# demo_dermis_main_testboard_dig.net
KiCad netlist of a schematic drawn in Altium Designer
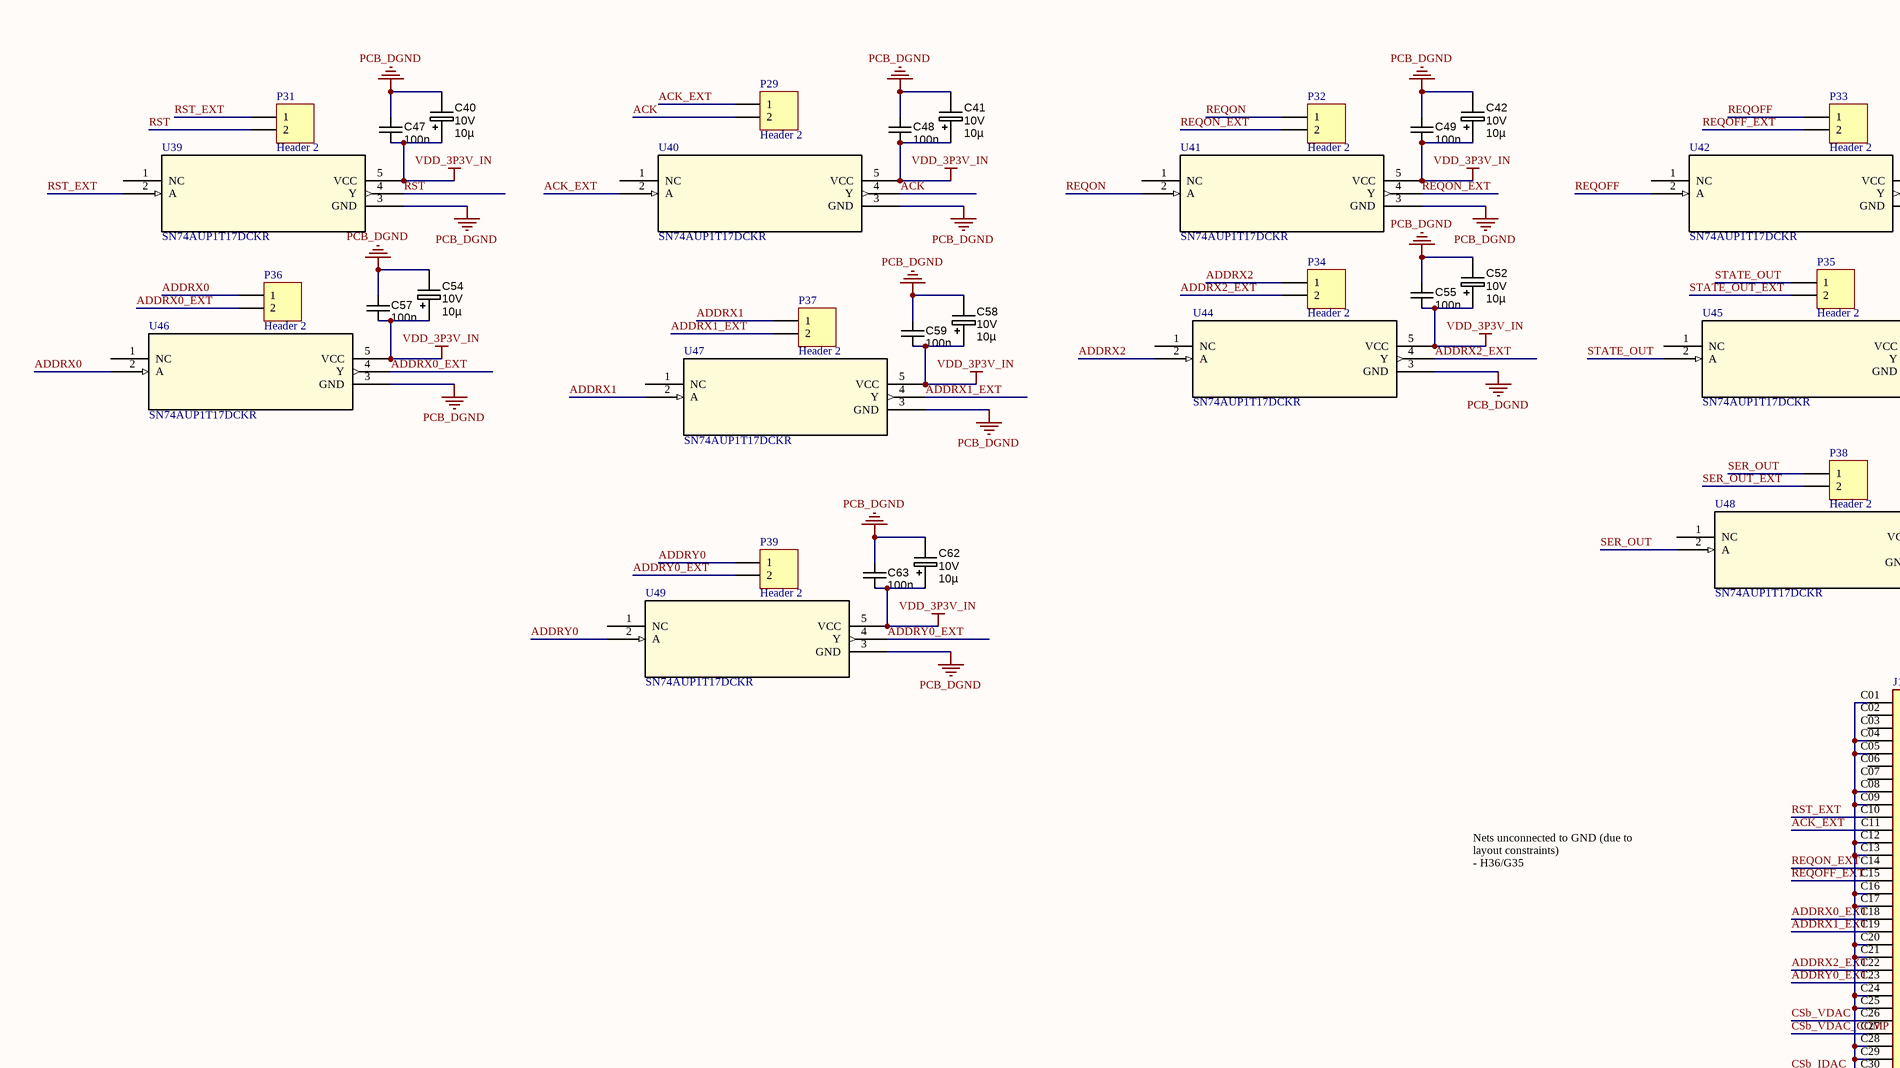
[diagram p0: demo_dermis_main_testboard_dig.SchDoc, top left]
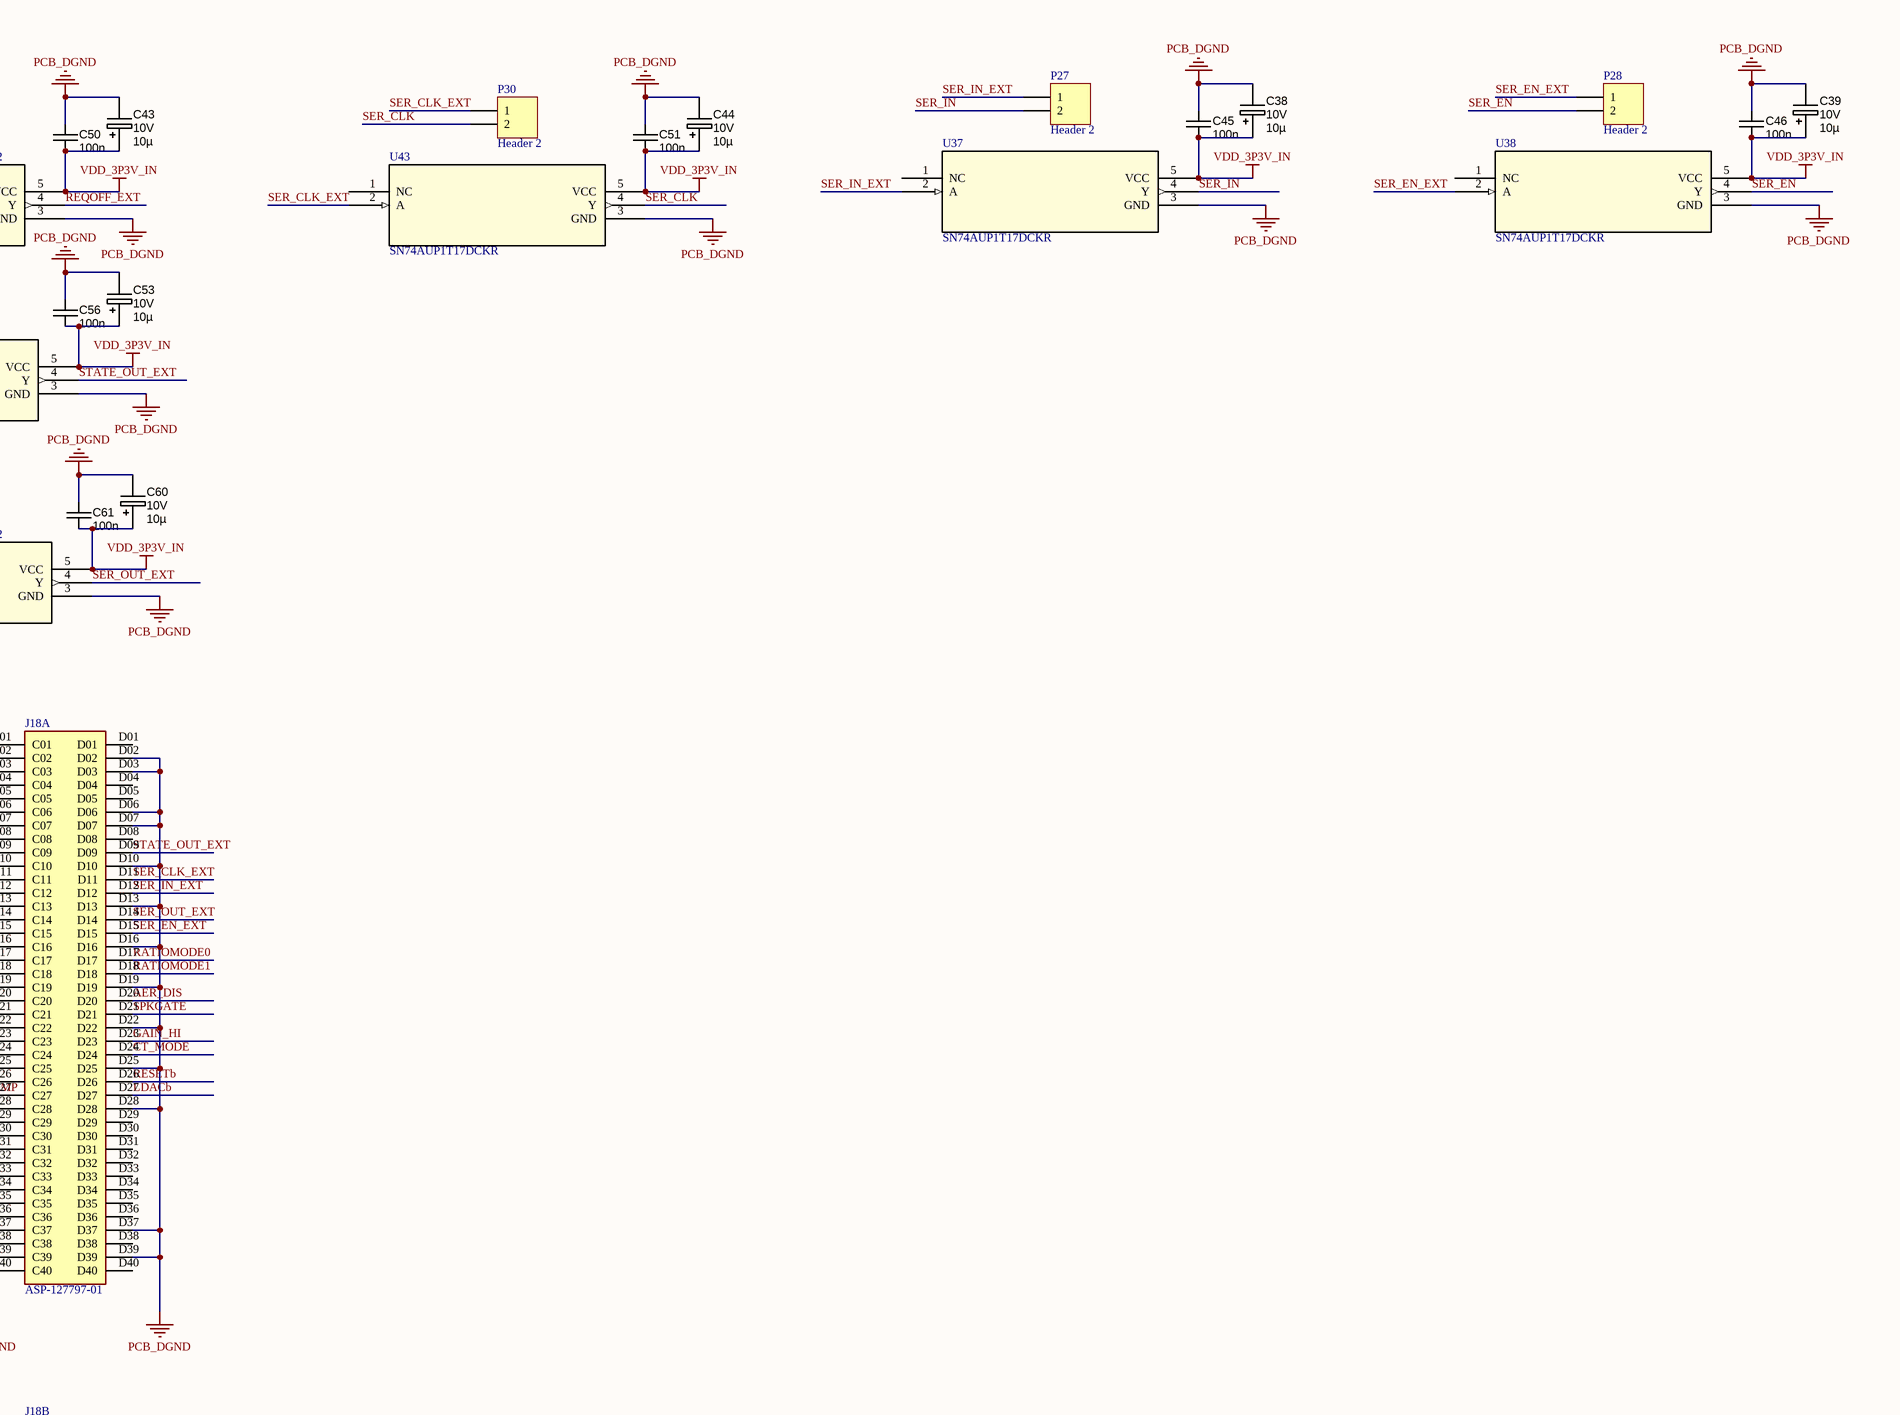
[diagram p1: demo_dermis_main_testboard_dig.SchDoc, top right]
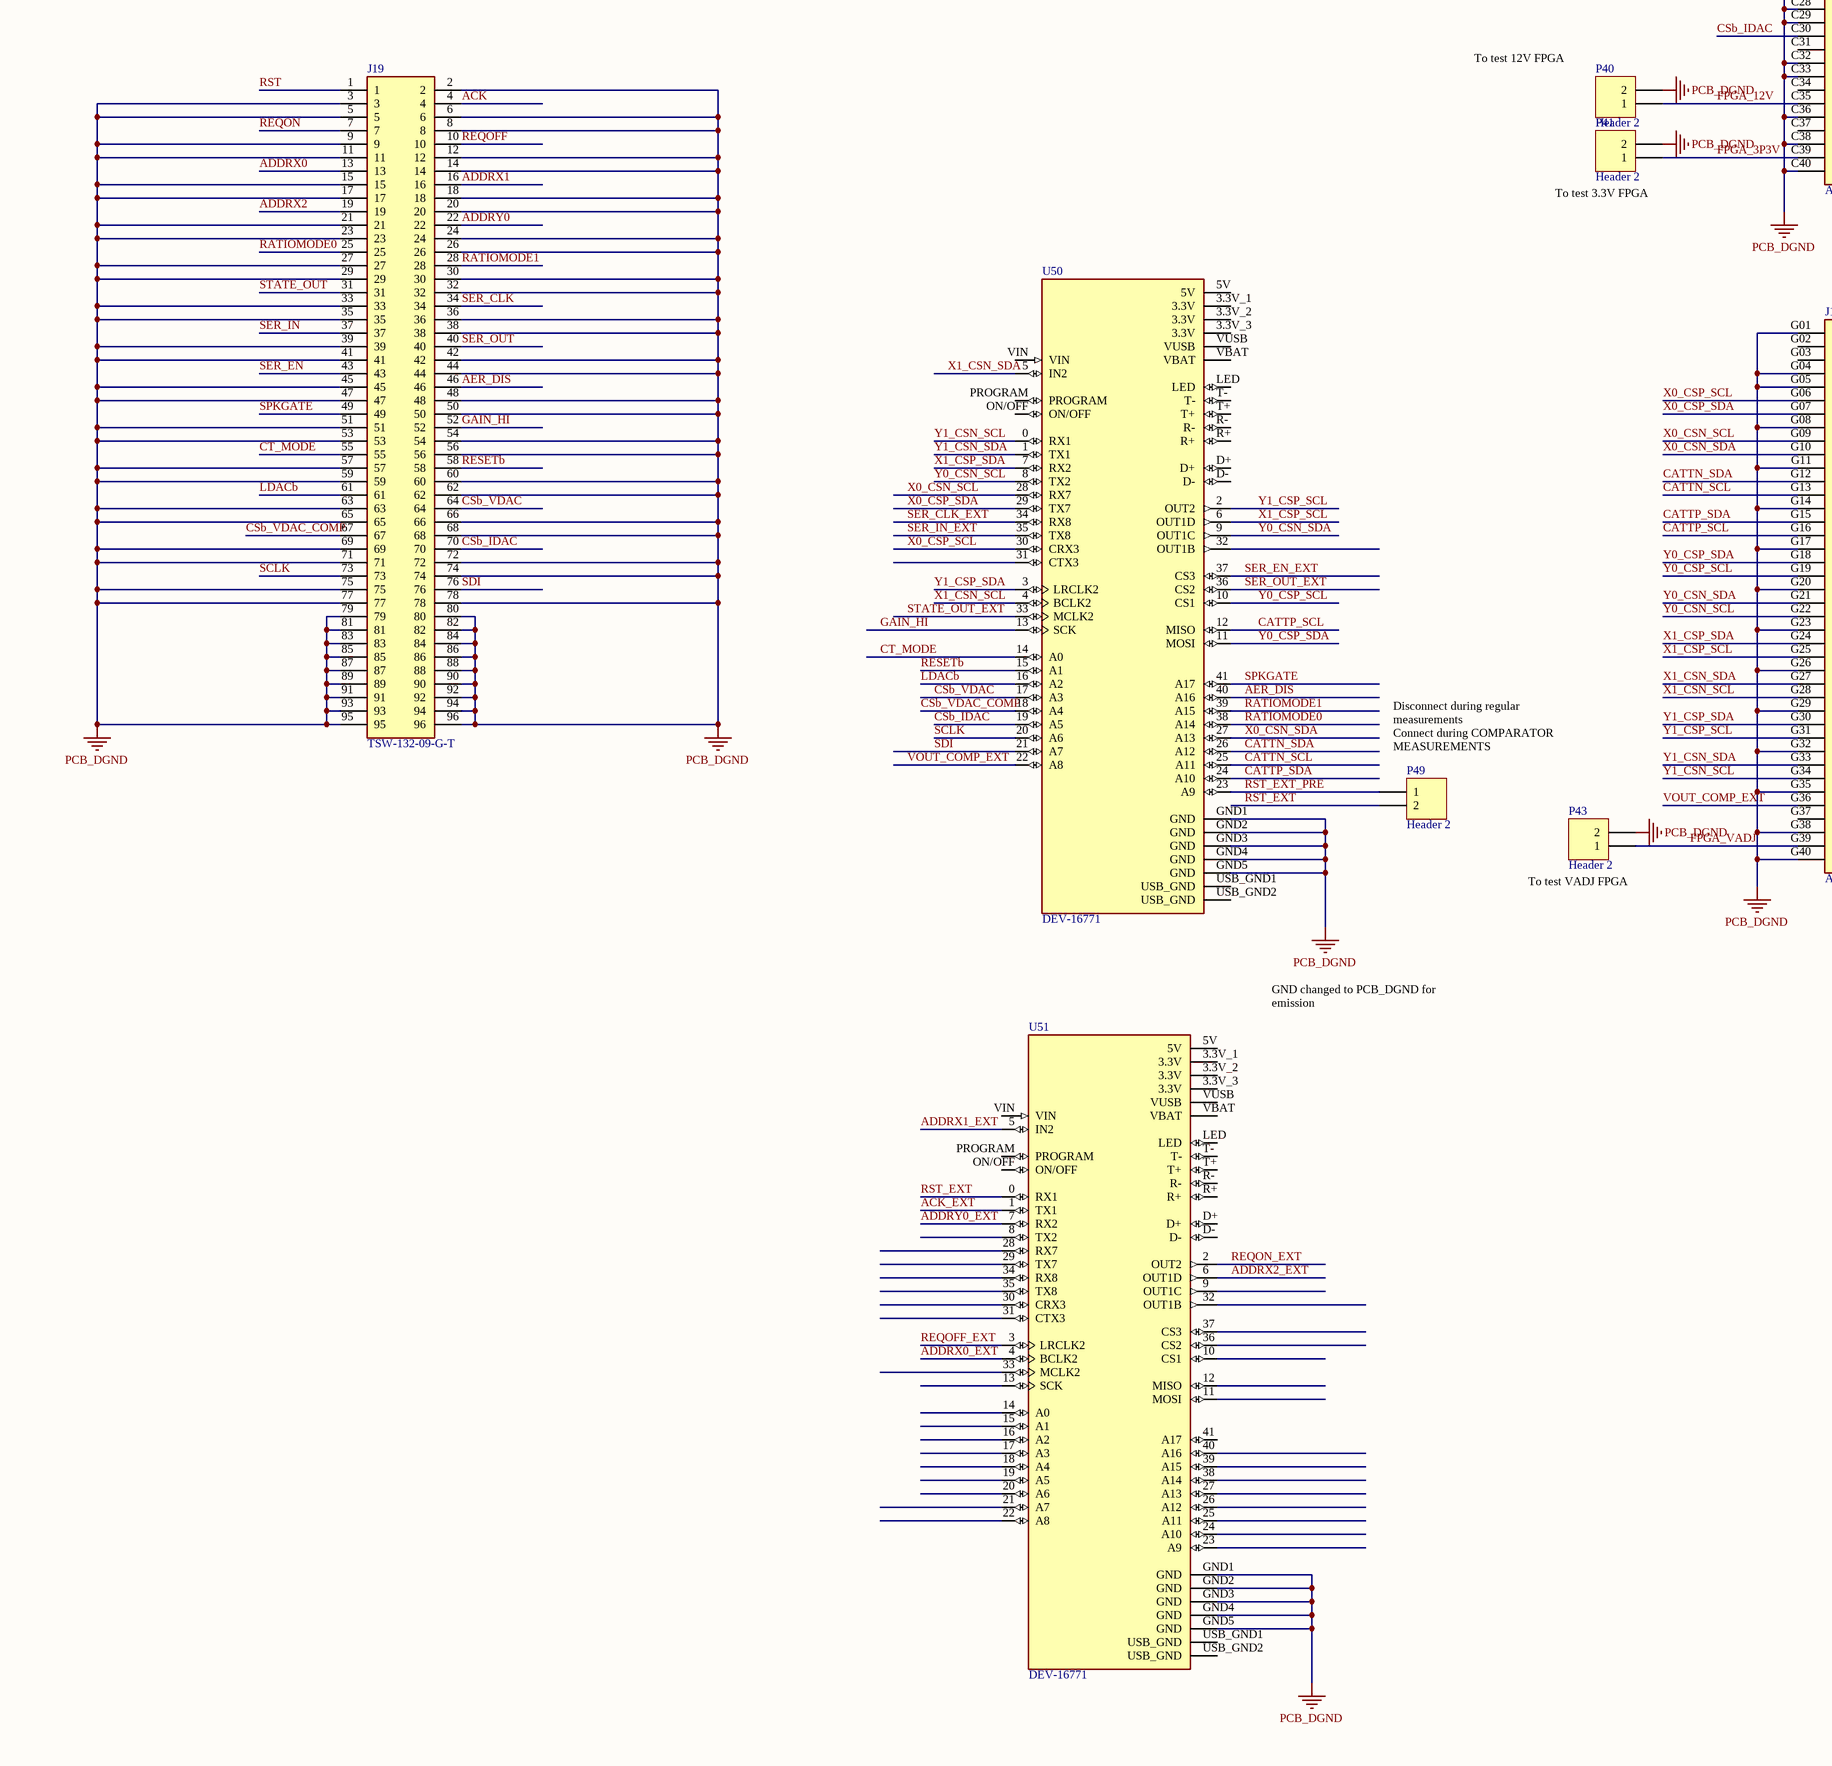
[diagram p2: demo_dermis_main_testboard_dig.SchDoc, bottom left]
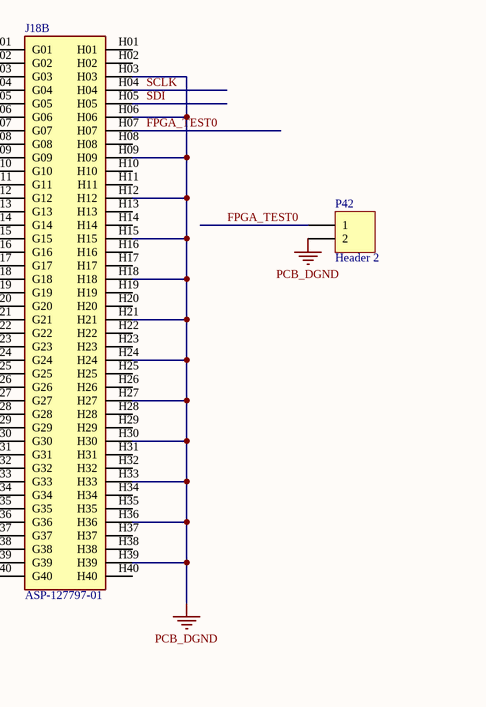
[diagram p3: demo_dermis_main_testboard_dig.SchDoc, bottom right]

(export (version "E")
  (design (tool "Eeschema 10.0.6"))
  (components
    (comp (ref "C38")
      (value "10µ")
      (footprint "CAPMP2012X150USR")
      (description "Capacitor SMD Tantalum 10uF 20% 10V 0805")
      (fields (field (name "TOLERANCE") "±20%") (field (name "RATINGS") "10V"))
      (libsource (lib "PBL - Capacitors") (part "CAPT_10u_0805_10V"))
    )
    (comp (ref "C39")
      (value "10µ")
      (footprint "CAPMP2012X150USR")
      (description "Capacitor SMD Tantalum 10uF 20% 10V 0805")
      (fields (field (name "TOLERANCE") "±20%") (field (name "RATINGS") "10V"))
      (libsource (lib "PBL - Capacitors") (part "CAPT_10u_0805_10V"))
    )
    (comp (ref "C40")
      (value "10µ")
      (footprint "CAPMP2012X150USR")
      (description "Capacitor SMD Tantalum 10uF 20% 10V 0805")
      (fields (field (name "TOLERANCE") "±20%") (field (name "RATINGS") "10V"))
      (libsource (lib "PBL - Capacitors") (part "CAPT_10u_0805_10V"))
    )
    (comp (ref "C41")
      (value "10µ")
      (footprint "CAPMP2012X150USR")
      (description "Capacitor SMD Tantalum 10uF 20% 10V 0805")
      (fields (field (name "TOLERANCE") "±20%") (field (name "RATINGS") "10V"))
      (libsource (lib "PBL - Capacitors") (part "CAPT_10u_0805_10V"))
    )
    (comp (ref "C42")
      (value "10µ")
      (footprint "CAPMP2012X150USR")
      (description "Capacitor SMD Tantalum 10uF 20% 10V 0805")
      (fields (field (name "TOLERANCE") "±20%") (field (name "RATINGS") "10V"))
      (libsource (lib "PBL - Capacitors") (part "CAPT_10u_0805_10V"))
    )
    (comp (ref "C43")
      (value "10µ")
      (footprint "CAPMP2012X150USR")
      (description "Capacitor SMD Tantalum 10uF 20% 10V 0805")
      (fields (field (name "TOLERANCE") "±20%") (field (name "RATINGS") "10V"))
      (libsource (lib "PBL - Capacitors") (part "CAPT_10u_0805_10V"))
    )
    (comp (ref "C44")
      (value "10µ")
      (footprint "CAPMP2012X150USR")
      (description "Capacitor SMD Tantalum 10uF 20% 10V 0805")
      (fields (field (name "TOLERANCE") "±20%") (field (name "RATINGS") "10V"))
      (libsource (lib "PBL - Capacitors") (part "CAPT_10u_0805_10V"))
    )
    (comp (ref "C45")
      (value "100n")
      (footprint "CAPC1608N")
      (description "Capacitor SMD Cer 100nF 10% 50V X7R 0603")
      (fields (field (name "TOLERANCE") "±10%") (field (name "Comment") "approved sub OK"))
      (libsource (lib "PBL - Capacitors") (part "CAPC_100n_0603"))
    )
    (comp (ref "C46")
      (value "100n")
      (footprint "CAPC1608N")
      (description "Capacitor SMD Cer 100nF 10% 50V X7R 0603")
      (fields (field (name "TOLERANCE") "±10%") (field (name "Comment") "approved sub OK"))
      (libsource (lib "PBL - Capacitors") (part "CAPC_100n_0603"))
    )
    (comp (ref "C47")
      (value "100n")
      (footprint "CAPC1608N")
      (description "Capacitor SMD Cer 100nF 10% 50V X7R 0603")
      (fields (field (name "TOLERANCE") "±10%") (field (name "Comment") "approved sub OK"))
      (libsource (lib "PBL - Capacitors") (part "CAPC_100n_0603"))
    )
    (comp (ref "C48")
      (value "100n")
      (footprint "CAPC1608N")
      (description "Capacitor SMD Cer 100nF 10% 50V X7R 0603")
      (fields (field (name "TOLERANCE") "±10%") (field (name "Comment") "approved sub OK"))
      (libsource (lib "PBL - Capacitors") (part "CAPC_100n_0603"))
    )
    (comp (ref "C49")
      (value "100n")
      (footprint "CAPC1608N")
      (description "Capacitor SMD Cer 100nF 10% 50V X7R 0603")
      (fields (field (name "TOLERANCE") "±10%") (field (name "Comment") "approved sub OK"))
      (libsource (lib "PBL - Capacitors") (part "CAPC_100n_0603"))
    )
    (comp (ref "C50")
      (value "100n")
      (footprint "CAPC1608N")
      (description "Capacitor SMD Cer 100nF 10% 50V X7R 0603")
      (fields (field (name "TOLERANCE") "±10%") (field (name "Comment") "approved sub OK"))
      (libsource (lib "PBL - Capacitors") (part "CAPC_100n_0603"))
    )
    (comp (ref "C51")
      (value "100n")
      (footprint "CAPC1608N")
      (description "Capacitor SMD Cer 100nF 10% 50V X7R 0603")
      (fields (field (name "TOLERANCE") "±10%") (field (name "Comment") "approved sub OK"))
      (libsource (lib "PBL - Capacitors") (part "CAPC_100n_0603"))
    )
    (comp (ref "C52")
      (value "10µ")
      (footprint "CAPMP2012X150USR")
      (description "Capacitor SMD Tantalum 10uF 20% 10V 0805")
      (fields (field (name "TOLERANCE") "±20%") (field (name "RATINGS") "10V"))
      (libsource (lib "PBL - Capacitors") (part "CAPT_10u_0805_10V"))
    )
    (comp (ref "C53")
      (value "10µ")
      (footprint "CAPMP2012X150USR")
      (description "Capacitor SMD Tantalum 10uF 20% 10V 0805")
      (fields (field (name "TOLERANCE") "±20%") (field (name "RATINGS") "10V"))
      (libsource (lib "PBL - Capacitors") (part "CAPT_10u_0805_10V"))
    )
    (comp (ref "C54")
      (value "10µ")
      (footprint "CAPMP2012X150USR")
      (description "Capacitor SMD Tantalum 10uF 20% 10V 0805")
      (fields (field (name "TOLERANCE") "±20%") (field (name "RATINGS") "10V"))
      (libsource (lib "PBL - Capacitors") (part "CAPT_10u_0805_10V"))
    )
    (comp (ref "C55")
      (value "100n")
      (footprint "CAPC1608N")
      (description "Capacitor SMD Cer 100nF 10% 50V X7R 0603")
      (fields (field (name "TOLERANCE") "±10%") (field (name "Comment") "approved sub OK"))
      (libsource (lib "PBL - Capacitors") (part "CAPC_100n_0603"))
    )
    (comp (ref "C56")
      (value "100n")
      (footprint "CAPC1608N")
      (description "Capacitor SMD Cer 100nF 10% 50V X7R 0603")
      (fields (field (name "TOLERANCE") "±10%") (field (name "Comment") "approved sub OK"))
      (libsource (lib "PBL - Capacitors") (part "CAPC_100n_0603"))
    )
    (comp (ref "C57")
      (value "100n")
      (footprint "CAPC1608N")
      (description "Capacitor SMD Cer 100nF 10% 50V X7R 0603")
      (fields (field (name "TOLERANCE") "±10%") (field (name "Comment") "approved sub OK"))
      (libsource (lib "PBL - Capacitors") (part "CAPC_100n_0603"))
    )
    (comp (ref "C58")
      (value "10µ")
      (footprint "CAPMP2012X150USR")
      (description "Capacitor SMD Tantalum 10uF 20% 10V 0805")
      (fields (field (name "TOLERANCE") "±20%") (field (name "RATINGS") "10V"))
      (libsource (lib "PBL - Capacitors") (part "CAPT_10u_0805_10V"))
    )
    (comp (ref "C59")
      (value "100n")
      (footprint "CAPC1608N")
      (description "Capacitor SMD Cer 100nF 10% 50V X7R 0603")
      (fields (field (name "TOLERANCE") "±10%") (field (name "Comment") "approved sub OK"))
      (libsource (lib "PBL - Capacitors") (part "CAPC_100n_0603"))
    )
    (comp (ref "C60")
      (value "10µ")
      (footprint "CAPMP2012X150USR")
      (description "Capacitor SMD Tantalum 10uF 20% 10V 0805")
      (fields (field (name "TOLERANCE") "±20%") (field (name "RATINGS") "10V"))
      (libsource (lib "PBL - Capacitors") (part "CAPT_10u_0805_10V"))
    )
    (comp (ref "C61")
      (value "100n")
      (footprint "CAPC1608N")
      (description "Capacitor SMD Cer 100nF 10% 50V X7R 0603")
      (fields (field (name "TOLERANCE") "±10%") (field (name "Comment") "approved sub OK"))
      (libsource (lib "PBL - Capacitors") (part "CAPC_100n_0603"))
    )
    (comp (ref "C62")
      (value "10µ")
      (footprint "CAPMP2012X150USR")
      (description "Capacitor SMD Tantalum 10uF 20% 10V 0805")
      (fields (field (name "TOLERANCE") "±20%") (field (name "RATINGS") "10V"))
      (libsource (lib "PBL - Capacitors") (part "CAPT_10u_0805_10V"))
    )
    (comp (ref "C63")
      (value "100n")
      (footprint "CAPC1608N")
      (description "Capacitor SMD Cer 100nF 10% 50V X7R 0603")
      (fields (field (name "TOLERANCE") "±10%") (field (name "Comment") "approved sub OK"))
      (libsource (lib "PBL - Capacitors") (part "CAPC_100n_0603"))
    )
    (comp (ref "J18")
      (value "ASP-127797-01")
      (footprint "SAMTEC_ASP-127797-01")
      (description "160 Position Connector Array, Male Pins Surface Mount Gold")
      (fields (field (name "MF") "Samtec Inc."))
      (libsource (lib "ASP-127797-01") (part "ASP-127797-01"))
    )
    (comp (ref "J19")
      (value "TSW-132-09-G-T")
      (footprint "HDRV96W64P254_3X32_8128X749X838P")
      (description "CONN HEADER 96 POS .100\"")
      (libsource (lib "HEADER_3x32") (part "TSW-132-09-G-T"))
    )
    (comp (ref "P27")
      (value "Header 2")
      (footprint "HDR1X2")
      (description "Header, 2-Pin")
      (fields (field (name "PUBLISHER") "Altium Limited"))
      (libsource (lib "Miscellaneous Connectors") (part "Header 2"))
    )
    (comp (ref "P28")
      (value "Header 2")
      (footprint "HDR1X2")
      (description "Header, 2-Pin")
      (fields (field (name "PUBLISHER") "Altium Limited"))
      (libsource (lib "Miscellaneous Connectors") (part "Header 2"))
    )
    (comp (ref "P29")
      (value "Header 2")
      (footprint "HDR1X2")
      (description "Header, 2-Pin")
      (fields (field (name "PUBLISHER") "Altium Limited"))
      (libsource (lib "Miscellaneous Connectors") (part "Header 2"))
    )
    (comp (ref "P30")
      (value "Header 2")
      (footprint "HDR1X2")
      (description "Header, 2-Pin")
      (fields (field (name "PUBLISHER") "Altium Limited"))
      (libsource (lib "Miscellaneous Connectors") (part "Header 2"))
    )
    (comp (ref "P31")
      (value "Header 2")
      (footprint "HDR1X2")
      (description "Header, 2-Pin")
      (fields (field (name "PUBLISHER") "Altium Limited"))
      (libsource (lib "Miscellaneous Connectors") (part "Header 2"))
    )
    (comp (ref "P32")
      (value "Header 2")
      (footprint "HDR1X2")
      (description "Header, 2-Pin")
      (fields (field (name "PUBLISHER") "Altium Limited"))
      (libsource (lib "Miscellaneous Connectors") (part "Header 2"))
    )
    (comp (ref "P33")
      (value "Header 2")
      (footprint "HDR1X2")
      (description "Header, 2-Pin")
      (fields (field (name "PUBLISHER") "Altium Limited"))
      (libsource (lib "Miscellaneous Connectors") (part "Header 2"))
    )
    (comp (ref "P34")
      (value "Header 2")
      (footprint "HDR1X2")
      (description "Header, 2-Pin")
      (fields (field (name "PUBLISHER") "Altium Limited"))
      (libsource (lib "Miscellaneous Connectors") (part "Header 2"))
    )
    (comp (ref "P35")
      (value "Header 2")
      (footprint "HDR1X2")
      (description "Header, 2-Pin")
      (fields (field (name "PUBLISHER") "Altium Limited"))
      (libsource (lib "Miscellaneous Connectors") (part "Header 2"))
    )
    (comp (ref "P36")
      (value "Header 2")
      (footprint "HDR1X2")
      (description "Header, 2-Pin")
      (fields (field (name "PUBLISHER") "Altium Limited"))
      (libsource (lib "Miscellaneous Connectors") (part "Header 2"))
    )
    (comp (ref "P37")
      (value "Header 2")
      (footprint "HDR1X2")
      (description "Header, 2-Pin")
      (fields (field (name "PUBLISHER") "Altium Limited"))
      (libsource (lib "Miscellaneous Connectors") (part "Header 2"))
    )
    (comp (ref "P38")
      (value "Header 2")
      (footprint "HDR1X2")
      (description "Header, 2-Pin")
      (fields (field (name "PUBLISHER") "Altium Limited"))
      (libsource (lib "Miscellaneous Connectors") (part "Header 2"))
    )
    (comp (ref "P39")
      (value "Header 2")
      (footprint "HDR1X2")
      (description "Header, 2-Pin")
      (fields (field (name "PUBLISHER") "Altium Limited"))
      (libsource (lib "Miscellaneous Connectors") (part "Header 2"))
    )
    (comp (ref "P40")
      (value "Header 2")
      (footprint "HDR1X2")
      (description "Header, 2-Pin")
      (fields (field (name "PUBLISHER") "Altium Limited"))
      (libsource (lib "") (part "Header 2_1"))
    )
    (comp (ref "P41")
      (value "Header 2")
      (footprint "HDR1X2")
      (description "Header, 2-Pin")
      (fields (field (name "PUBLISHER") "Altium Limited"))
      (libsource (lib "") (part "Header 2_1"))
    )
    (comp (ref "P42")
      (value "Header 2")
      (footprint "HDR1X2")
      (description "Header, 2-Pin")
      (fields (field (name "PUBLISHER") "Altium Limited"))
      (libsource (lib "Miscellaneous Connectors") (part "Header 2"))
    )
    (comp (ref "P43")
      (value "Header 2")
      (footprint "HDR1X2")
      (description "Header, 2-Pin")
      (fields (field (name "PUBLISHER") "Altium Limited"))
      (libsource (lib "") (part "Header 2_1"))
    )
    (comp (ref "P49")
      (value "Header 2")
      (footprint "HDR1X2")
      (description "Header, 2-Pin")
      (fields (field (name "PUBLISHER") "Altium Limited"))
      (libsource (lib "Miscellaneous Connectors") (part "Header 2"))
    )
    (comp (ref "U37")
      (value "SN74AUP1T17DCKR")
      (footprint "DCK5")
      (description "No Description Available")
      (libsource (lib "SN74AUP1T17DCKR") (part "SN74AUP1T17DCKR"))
    )
    (comp (ref "U38")
      (value "SN74AUP1T17DCKR")
      (footprint "DCK5")
      (description "No Description Available")
      (libsource (lib "SN74AUP1T17DCKR") (part "SN74AUP1T17DCKR"))
    )
    (comp (ref "U39")
      (value "SN74AUP1T17DCKR")
      (footprint "DCK5")
      (description "No Description Available")
      (libsource (lib "SN74AUP1T17DCKR") (part "SN74AUP1T17DCKR"))
    )
    (comp (ref "U40")
      (value "SN74AUP1T17DCKR")
      (footprint "DCK5")
      (description "No Description Available")
      (libsource (lib "SN74AUP1T17DCKR") (part "SN74AUP1T17DCKR"))
    )
    (comp (ref "U41")
      (value "SN74AUP1T17DCKR")
      (footprint "DCK5")
      (description "No Description Available")
      (libsource (lib "SN74AUP1T17DCKR") (part "SN74AUP1T17DCKR"))
    )
    (comp (ref "U42")
      (value "SN74AUP1T17DCKR")
      (footprint "DCK5")
      (description "No Description Available")
      (libsource (lib "SN74AUP1T17DCKR") (part "SN74AUP1T17DCKR"))
    )
    (comp (ref "U43")
      (value "SN74AUP1T17DCKR")
      (footprint "DCK5")
      (description "No Description Available")
      (libsource (lib "SN74AUP1T17DCKR") (part "SN74AUP1T17DCKR"))
    )
    (comp (ref "U44")
      (value "SN74AUP1T17DCKR")
      (footprint "DCK5")
      (description "No Description Available")
      (libsource (lib "SN74AUP1T17DCKR") (part "SN74AUP1T17DCKR"))
    )
    (comp (ref "U45")
      (value "SN74AUP1T17DCKR")
      (footprint "DCK5")
      (description "No Description Available")
      (libsource (lib "SN74AUP1T17DCKR") (part "SN74AUP1T17DCKR"))
    )
    (comp (ref "U46")
      (value "SN74AUP1T17DCKR")
      (footprint "DCK5")
      (description "No Description Available")
      (libsource (lib "SN74AUP1T17DCKR") (part "SN74AUP1T17DCKR"))
    )
    (comp (ref "U47")
      (value "SN74AUP1T17DCKR")
      (footprint "DCK5")
      (description "No Description Available")
      (libsource (lib "SN74AUP1T17DCKR") (part "SN74AUP1T17DCKR"))
    )
    (comp (ref "U48")
      (value "SN74AUP1T17DCKR")
      (footprint "DCK5")
      (description "No Description Available")
      (libsource (lib "SN74AUP1T17DCKR") (part "SN74AUP1T17DCKR"))
    )
    (comp (ref "U49")
      (value "SN74AUP1T17DCKR")
      (footprint "DCK5")
      (description "No Description Available")
      (libsource (lib "SN74AUP1T17DCKR") (part "SN74AUP1T17DCKR"))
    )
    (comp (ref "U50")
      (value "DEV-16771")
      (footprint "MODULE_DEV-16771")
      (description "RT1062 Teensy 4.1 series ARM® Cortex®-M7 MPU Embedded Evaluation Board")
      (fields (field (name "MF") "SparkFun Electronics"))
      (libsource (lib "DEV-16771") (part "DEV-16771"))
    )
    (comp (ref "U51")
      (value "DEV-16771")
      (footprint "MODULE_DEV-16771")
      (description "RT1062 Teensy 4.1 series ARM® Cortex®-M7 MPU Embedded Evaluation Board")
      (fields (field (name "MF") "SparkFun Electronics"))
      (libsource (lib "DEV-16771") (part "DEV-16771"))
    )
  )
  (nets
    (net (code "2") (name "/ACK") (class "Default")
      (node (ref "J19") (pin "4") (pinfunction "4_4") (pintype "passive"))
      (node (ref "P29") (pin "2") (pinfunction "2_2") (pintype "passive"))
      (node (ref "U40") (pin "4") (pinfunction "Y_4") (pintype "output"))
    )
    (net (code "3") (name "/ACK_EXT") (class "Default")
      (node (ref "J18") (pin "C11") (pinfunction "C11_C11") (pintype "passive"))
      (node (ref "P29") (pin "1") (pinfunction "1_1") (pintype "passive"))
      (node (ref "U40") (pin "2") (pinfunction "A_2") (pintype "input"))
      (node (ref "U51") (pin "1") (pinfunction "TX1_1") (pintype "bidirectional"))
    )
    (net (code "4") (name "/ADDRX0") (class "Default")
      (node (ref "J19") (pin "13") (pinfunction "13_13") (pintype "passive"))
      (node (ref "P36") (pin "1") (pinfunction "1_1") (pintype "passive"))
      (node (ref "U46") (pin "2") (pinfunction "A_2") (pintype "input"))
    )
    (net (code "5") (name "/ADDRX0_EXT") (class "Default")
      (node (ref "J18") (pin "C18") (pinfunction "C18_C18") (pintype "passive"))
      (node (ref "P36") (pin "2") (pinfunction "2_2") (pintype "passive"))
      (node (ref "U46") (pin "4") (pinfunction "Y_4") (pintype "output"))
      (node (ref "U51") (pin "4") (pinfunction "BCLK2_4") (pintype "bidirectional"))
    )
    (net (code "6") (name "/ADDRX1") (class "Default")
      (node (ref "J19") (pin "16") (pinfunction "16_16") (pintype "passive"))
      (node (ref "P37") (pin "1") (pinfunction "1_1") (pintype "passive"))
      (node (ref "U47") (pin "2") (pinfunction "A_2") (pintype "input"))
    )
    (net (code "7") (name "/ADDRX1_EXT") (class "Default")
      (node (ref "J18") (pin "C19") (pinfunction "C19_C19") (pintype "passive"))
      (node (ref "P37") (pin "2") (pinfunction "2_2") (pintype "passive"))
      (node (ref "U47") (pin "4") (pinfunction "Y_4") (pintype "output"))
      (node (ref "U51") (pin "5") (pinfunction "IN2_5") (pintype "bidirectional"))
    )
    (net (code "8") (name "/ADDRX2") (class "Default")
      (node (ref "J19") (pin "19") (pinfunction "19_19") (pintype "passive"))
      (node (ref "P34") (pin "1") (pinfunction "1_1") (pintype "passive"))
      (node (ref "U44") (pin "2") (pinfunction "A_2") (pintype "input"))
    )
    (net (code "9") (name "/ADDRX2_EXT") (class "Default")
      (node (ref "J18") (pin "C22") (pinfunction "C22_C22") (pintype "passive"))
      (node (ref "P34") (pin "2") (pinfunction "2_2") (pintype "passive"))
      (node (ref "U44") (pin "4") (pinfunction "Y_4") (pintype "output"))
      (node (ref "U51") (pin "6") (pinfunction "OUT1D_6") (pintype "output"))
    )
    (net (code "10") (name "/ADDRY0") (class "Default")
      (node (ref "J19") (pin "22") (pinfunction "22_22") (pintype "passive"))
      (node (ref "P39") (pin "1") (pinfunction "1_1") (pintype "passive"))
      (node (ref "U49") (pin "2") (pinfunction "A_2") (pintype "input"))
    )
    (net (code "11") (name "/ADDRY0_EXT") (class "Default")
      (node (ref "J18") (pin "C23") (pinfunction "C23_C23") (pintype "passive"))
      (node (ref "P39") (pin "2") (pinfunction "2_2") (pintype "passive"))
      (node (ref "U49") (pin "4") (pinfunction "Y_4") (pintype "output"))
      (node (ref "U51") (pin "7") (pinfunction "RX2_7") (pintype "bidirectional"))
    )
    (net (code "12") (name "/AER_DIS") (class "Default")
      (node (ref "J18") (pin "D20") (pinfunction "D20_D20") (pintype "passive"))
      (node (ref "J19") (pin "46") (pinfunction "46_46") (pintype "passive"))
      (node (ref "U50") (pin "40") (pinfunction "A16_40") (pintype "bidirectional"))
    )
    (net (code "13") (name "/CATTN_SCL") (class "Default")
      (node (ref "J18") (pin "G13") (pinfunction "G13_G13") (pintype "passive"))
      (node (ref "U50") (pin "25") (pinfunction "A11_25") (pintype "bidirectional"))
    )
    (net (code "14") (name "/CATTN_SDA") (class "Default")
      (node (ref "J18") (pin "G12") (pinfunction "G12_G12") (pintype "passive"))
      (node (ref "U50") (pin "26") (pinfunction "A12_26") (pintype "bidirectional"))
    )
    (net (code "15") (name "/CATTP_SCL") (class "Default")
      (node (ref "J18") (pin "G16") (pinfunction "G16_G16") (pintype "passive"))
      (node (ref "U50") (pin "12") (pinfunction "MISO_12") (pintype "bidirectional"))
    )
    (net (code "16") (name "/CATTP_SDA") (class "Default")
      (node (ref "J18") (pin "G15") (pinfunction "G15_G15") (pintype "passive"))
      (node (ref "U50") (pin "24") (pinfunction "A10_24") (pintype "bidirectional"))
    )
    (net (code "17") (name "/CSb_IDAC") (class "Default")
      (node (ref "J18") (pin "C30") (pinfunction "C30_C30") (pintype "passive"))
      (node (ref "J19") (pin "70") (pinfunction "70_70") (pintype "passive"))
      (node (ref "U50") (pin "19") (pinfunction "A5_19") (pintype "bidirectional"))
    )
    (net (code "18") (name "/CSb_VDAC") (class "Default")
      (node (ref "J18") (pin "C26") (pinfunction "C26_C26") (pintype "passive"))
      (node (ref "J19") (pin "64") (pinfunction "64_64") (pintype "passive"))
      (node (ref "U50") (pin "17") (pinfunction "A3_17") (pintype "bidirectional"))
    )
    (net (code "19") (name "/CSb_VDAC_COMP") (class "Default")
      (node (ref "J18") (pin "C27") (pinfunction "C27_C27") (pintype "passive"))
      (node (ref "J19") (pin "67") (pinfunction "67_67") (pintype "passive"))
      (node (ref "U50") (pin "18") (pinfunction "A4_18") (pintype "bidirectional"))
    )
    (net (code "20") (name "/CT_MODE") (class "Default")
      (node (ref "J18") (pin "D24") (pinfunction "D24_D24") (pintype "passive"))
      (node (ref "J19") (pin "55") (pinfunction "55_55") (pintype "passive"))
      (node (ref "U50") (pin "14") (pinfunction "A0_14") (pintype "bidirectional"))
    )
    (net (code "21") (name "/FPGA_3P3V") (class "Default")
      (node (ref "J18") (pin "C39") (pinfunction "C39_C39") (pintype "passive"))
      (node (ref "P41") (pin "1") (pinfunction "1_1") (pintype "passive"))
    )
    (net (code "22") (name "/FPGA_12V") (class "Default")
      (node (ref "J18") (pin "C35") (pinfunction "C35_C35") (pintype "passive"))
      (node (ref "P40") (pin "1") (pinfunction "1_1") (pintype "passive"))
    )
    (net (code "23") (name "/FPGA_TEST0") (class "Default")
      (node (ref "J18") (pin "H07") (pinfunction "H07_H07") (pintype "passive"))
      (node (ref "P42") (pin "1") (pinfunction "1_1") (pintype "passive"))
    )
    (net (code "24") (name "/FPGA_VADJ") (class "Default")
      (node (ref "J18") (pin "G39") (pinfunction "G39_G39") (pintype "passive"))
      (node (ref "P43") (pin "1") (pinfunction "1_1") (pintype "passive"))
    )
    (net (code "25") (name "/GAIN_HI") (class "Default")
      (node (ref "J18") (pin "D23") (pinfunction "D23_D23") (pintype "passive"))
      (node (ref "J19") (pin "52") (pinfunction "52_52") (pintype "passive"))
      (node (ref "U50") (pin "13") (pinfunction "SCK_13") (pintype "bidirectional"))
    )
    (net (code "26") (name "/LDACb") (class "Default")
      (node (ref "J18") (pin "D27") (pinfunction "D27_D27") (pintype "passive"))
      (node (ref "J19") (pin "61") (pinfunction "61_61") (pintype "passive"))
      (node (ref "U50") (pin "16") (pinfunction "A2_16") (pintype "bidirectional"))
    )
    (net (code "27") (name "/RATIOMODE0") (class "Default")
      (node (ref "J18") (pin "D17") (pinfunction "D17_D17") (pintype "passive"))
      (node (ref "J19") (pin "25") (pinfunction "25_25") (pintype "passive"))
      (node (ref "U50") (pin "38") (pinfunction "A14_38") (pintype "bidirectional"))
    )
    (net (code "28") (name "/RATIOMODE1") (class "Default")
      (node (ref "J18") (pin "D18") (pinfunction "D18_D18") (pintype "passive"))
      (node (ref "J19") (pin "28") (pinfunction "28_28") (pintype "passive"))
      (node (ref "U50") (pin "39") (pinfunction "A15_39") (pintype "bidirectional"))
    )
    (net (code "29") (name "/REQOFF") (class "Default")
      (node (ref "J19") (pin "10") (pinfunction "10_10") (pintype "passive"))
      (node (ref "P33") (pin "1") (pinfunction "1_1") (pintype "passive"))
      (node (ref "U42") (pin "2") (pinfunction "A_2") (pintype "input"))
    )
    (net (code "30") (name "/REQOFF_EXT") (class "Default")
      (node (ref "J18") (pin "C15") (pinfunction "C15_C15") (pintype "passive"))
      (node (ref "P33") (pin "2") (pinfunction "2_2") (pintype "passive"))
      (node (ref "U42") (pin "4") (pinfunction "Y_4") (pintype "output"))
      (node (ref "U51") (pin "3") (pinfunction "LRCLK2_3") (pintype "bidirectional"))
    )
    (net (code "31") (name "/REQON") (class "Default")
      (node (ref "J19") (pin "7") (pinfunction "7_7") (pintype "passive"))
      (node (ref "P32") (pin "1") (pinfunction "1_1") (pintype "passive"))
      (node (ref "U41") (pin "2") (pinfunction "A_2") (pintype "input"))
    )
    (net (code "32") (name "/REQON_EXT") (class "Default")
      (node (ref "J18") (pin "C14") (pinfunction "C14_C14") (pintype "passive"))
      (node (ref "P32") (pin "2") (pinfunction "2_2") (pintype "passive"))
      (node (ref "U41") (pin "4") (pinfunction "Y_4") (pintype "output"))
      (node (ref "U51") (pin "2") (pinfunction "OUT2_2") (pintype "output"))
    )
    (net (code "33") (name "/RESETb") (class "Default")
      (node (ref "J18") (pin "D26") (pinfunction "D26_D26") (pintype "passive"))
      (node (ref "J19") (pin "58") (pinfunction "58_58") (pintype "passive"))
      (node (ref "U50") (pin "15") (pinfunction "A1_15") (pintype "bidirectional"))
    )
    (net (code "34") (name "/RST") (class "Default")
      (node (ref "J19") (pin "1") (pinfunction "1_1") (pintype "passive"))
      (node (ref "P31") (pin "2") (pinfunction "2_2") (pintype "passive"))
      (node (ref "U39") (pin "4") (pinfunction "Y_4") (pintype "output"))
    )
    (net (code "35") (name "/RST_EXT") (class "Default")
      (node (ref "J18") (pin "C10") (pinfunction "C10_C10") (pintype "passive"))
      (node (ref "P31") (pin "1") (pinfunction "1_1") (pintype "passive"))
      (node (ref "P49") (pin "2") (pinfunction "2_2") (pintype "passive"))
      (node (ref "U39") (pin "2") (pinfunction "A_2") (pintype "input"))
      (node (ref "U51") (pin "0") (pinfunction "RX1_0") (pintype "bidirectional"))
    )
    (net (code "36") (name "/RST_EXT_PRE") (class "Default")
      (node (ref "P49") (pin "1") (pinfunction "1_1") (pintype "passive"))
      (node (ref "U50") (pin "23") (pinfunction "A9_23") (pintype "bidirectional"))
    )
    (net (code "37") (name "/SCLK") (class "Default")
      (node (ref "J18") (pin "H04") (pinfunction "H04_H04") (pintype "passive"))
      (node (ref "J19") (pin "73") (pinfunction "73_73") (pintype "passive"))
      (node (ref "U50") (pin "20") (pinfunction "A6_20") (pintype "bidirectional"))
    )
    (net (code "38") (name "/SDI") (class "Default")
      (node (ref "J18") (pin "H05") (pinfunction "H05_H05") (pintype "passive"))
      (node (ref "J19") (pin "76") (pinfunction "76_76") (pintype "passive"))
      (node (ref "U50") (pin "21") (pinfunction "A7_21") (pintype "bidirectional"))
    )
    (net (code "39") (name "/SER_CLK") (class "Default")
      (node (ref "J19") (pin "34") (pinfunction "34_34") (pintype "passive"))
      (node (ref "P30") (pin "2") (pinfunction "2_2") (pintype "passive"))
      (node (ref "U43") (pin "4") (pinfunction "Y_4") (pintype "output"))
    )
    (net (code "40") (name "/SER_CLK_EXT") (class "Default")
      (node (ref "J18") (pin "D11") (pinfunction "D11_D11") (pintype "passive"))
      (node (ref "P30") (pin "1") (pinfunction "1_1") (pintype "passive"))
      (node (ref "U43") (pin "2") (pinfunction "A_2") (pintype "input"))
      (node (ref "U50") (pin "34") (pinfunction "RX8_34") (pintype "bidirectional"))
    )
    (net (code "41") (name "/SER_EN") (class "Default")
      (node (ref "J19") (pin "43") (pinfunction "43_43") (pintype "passive"))
      (node (ref "P28") (pin "2") (pinfunction "2_2") (pintype "passive"))
      (node (ref "U38") (pin "4") (pinfunction "Y_4") (pintype "output"))
    )
    (net (code "42") (name "/SER_EN_EXT") (class "Default")
      (node (ref "J18") (pin "D15") (pinfunction "D15_D15") (pintype "passive"))
      (node (ref "P28") (pin "1") (pinfunction "1_1") (pintype "passive"))
      (node (ref "U38") (pin "2") (pinfunction "A_2") (pintype "input"))
      (node (ref "U50") (pin "37") (pinfunction "CS3_37") (pintype "bidirectional"))
    )
    (net (code "43") (name "/SER_IN") (class "Default")
      (node (ref "J19") (pin "37") (pinfunction "37_37") (pintype "passive"))
      (node (ref "P27") (pin "2") (pinfunction "2_2") (pintype "passive"))
      (node (ref "U37") (pin "4") (pinfunction "Y_4") (pintype "output"))
    )
    (net (code "44") (name "/SER_IN_EXT") (class "Default")
      (node (ref "J18") (pin "D12") (pinfunction "D12_D12") (pintype "passive"))
      (node (ref "P27") (pin "1") (pinfunction "1_1") (pintype "passive"))
      (node (ref "U37") (pin "2") (pinfunction "A_2") (pintype "input"))
      (node (ref "U50") (pin "35") (pinfunction "TX8_35") (pintype "bidirectional"))
    )
    (net (code "45") (name "/SER_OUT") (class "Default")
      (node (ref "J19") (pin "40") (pinfunction "40_40") (pintype "passive"))
      (node (ref "P38") (pin "1") (pinfunction "1_1") (pintype "passive"))
      (node (ref "U48") (pin "2") (pinfunction "A_2") (pintype "input"))
    )
    (net (code "46") (name "/SER_OUT_EXT") (class "Default")
      (node (ref "J18") (pin "D14") (pinfunction "D14_D14") (pintype "passive"))
      (node (ref "P38") (pin "2") (pinfunction "2_2") (pintype "passive"))
      (node (ref "U48") (pin "4") (pinfunction "Y_4") (pintype "output"))
      (node (ref "U50") (pin "36") (pinfunction "CS2_36") (pintype "bidirectional"))
    )
    (net (code "47") (name "/SPKGATE") (class "Default")
      (node (ref "J18") (pin "D21") (pinfunction "D21_D21") (pintype "passive"))
      (node (ref "J19") (pin "49") (pinfunction "49_49") (pintype "passive"))
      (node (ref "U50") (pin "41") (pinfunction "A17_41") (pintype "bidirectional"))
    )
    (net (code "48") (name "/STATE_OUT") (class "Default")
      (node (ref "J19") (pin "31") (pinfunction "31_31") (pintype "passive"))
      (node (ref "P35") (pin "1") (pinfunction "1_1") (pintype "passive"))
      (node (ref "U45") (pin "2") (pinfunction "A_2") (pintype "input"))
    )
    (net (code "49") (name "/STATE_OUT_EXT") (class "Default")
      (node (ref "J18") (pin "D09") (pinfunction "D09_D09") (pintype "passive"))
      (node (ref "P35") (pin "2") (pinfunction "2_2") (pintype "passive"))
      (node (ref "U45") (pin "4") (pinfunction "Y_4") (pintype "output"))
      (node (ref "U50") (pin "33") (pinfunction "MCLK2_33") (pintype "bidirectional"))
    )
    (net (code "50") (name "/VOUT_COMP_EXT") (class "Default")
      (node (ref "J18") (pin "G36") (pinfunction "G36_G36") (pintype "passive"))
      (node (ref "U50") (pin "22") (pinfunction "A8_22") (pintype "bidirectional"))
    )
    (net (code "51") (name "/X0_CSN_SCL") (class "Default")
      (node (ref "J18") (pin "G09") (pinfunction "G09_G09") (pintype "passive"))
      (node (ref "U50") (pin "28") (pinfunction "RX7_28") (pintype "bidirectional"))
    )
    (net (code "52") (name "/X0_CSN_SDA") (class "Default")
      (node (ref "J18") (pin "G10") (pinfunction "G10_G10") (pintype "passive"))
      (node (ref "U50") (pin "27") (pinfunction "A13_27") (pintype "bidirectional"))
    )
    (net (code "53") (name "/X0_CSP_SCL") (class "Default")
      (node (ref "J18") (pin "G06") (pinfunction "G06_G06") (pintype "passive"))
      (node (ref "U50") (pin "30") (pinfunction "CRX3_30") (pintype "bidirectional"))
    )
    (net (code "54") (name "/X0_CSP_SDA") (class "Default")
      (node (ref "J18") (pin "G07") (pinfunction "G07_G07") (pintype "passive"))
      (node (ref "U50") (pin "29") (pinfunction "TX7_29") (pintype "bidirectional"))
    )
    (net (code "55") (name "/X1_CSN_SCL") (class "Default")
      (node (ref "J18") (pin "G28") (pinfunction "G28_G28") (pintype "passive"))
      (node (ref "U50") (pin "4") (pinfunction "BCLK2_4") (pintype "bidirectional"))
    )
    (net (code "56") (name "/X1_CSN_SDA") (class "Default")
      (node (ref "J18") (pin "G27") (pinfunction "G27_G27") (pintype "passive"))
      (node (ref "U50") (pin "5") (pinfunction "IN2_5") (pintype "bidirectional"))
    )
    (net (code "57") (name "/X1_CSP_SCL") (class "Default")
      (node (ref "J18") (pin "G25") (pinfunction "G25_G25") (pintype "passive"))
      (node (ref "U50") (pin "6") (pinfunction "OUT1D_6") (pintype "output"))
    )
    (net (code "58") (name "/X1_CSP_SDA") (class "Default")
      (node (ref "J18") (pin "G24") (pinfunction "G24_G24") (pintype "passive"))
      (node (ref "U50") (pin "7") (pinfunction "RX2_7") (pintype "bidirectional"))
    )
    (net (code "59") (name "/Y0_CSN_SCL") (class "Default")
      (node (ref "J18") (pin "G22") (pinfunction "G22_G22") (pintype "passive"))
      (node (ref "U50") (pin "8") (pinfunction "TX2_8") (pintype "bidirectional"))
    )
    (net (code "60") (name "/Y0_CSN_SDA") (class "Default")
      (node (ref "J18") (pin "G21") (pinfunction "G21_G21") (pintype "passive"))
      (node (ref "U50") (pin "9") (pinfunction "OUT1C_9") (pintype "output"))
    )
    (net (code "61") (name "/Y0_CSP_SCL") (class "Default")
      (node (ref "J18") (pin "G19") (pinfunction "G19_G19") (pintype "passive"))
      (node (ref "U50") (pin "10") (pinfunction "CS1_10") (pintype "bidirectional"))
    )
    (net (code "62") (name "/Y0_CSP_SDA") (class "Default")
      (node (ref "J18") (pin "G18") (pinfunction "G18_G18") (pintype "passive"))
      (node (ref "U50") (pin "11") (pinfunction "MOSI_11") (pintype "bidirectional"))
    )
    (net (code "63") (name "/Y1_CSN_SCL") (class "Default")
      (node (ref "J18") (pin "G34") (pinfunction "G34_G34") (pintype "passive"))
      (node (ref "U50") (pin "0") (pinfunction "RX1_0") (pintype "bidirectional"))
    )
    (net (code "64") (name "/Y1_CSN_SDA") (class "Default")
      (node (ref "J18") (pin "G33") (pinfunction "G33_G33") (pintype "passive"))
      (node (ref "U50") (pin "1") (pinfunction "TX1_1") (pintype "bidirectional"))
    )
    (net (code "65") (name "/Y1_CSP_SCL") (class "Default")
      (node (ref "J18") (pin "G31") (pinfunction "G31_G31") (pintype "passive"))
      (node (ref "U50") (pin "2") (pinfunction "OUT2_2") (pintype "output"))
    )
    (net (code "66") (name "/Y1_CSP_SDA") (class "Default")
      (node (ref "J18") (pin "G30") (pinfunction "G30_G30") (pintype "passive"))
      (node (ref "U50") (pin "3") (pinfunction "LRCLK2_3") (pintype "bidirectional"))
    )
    (net (code "67") (name "PCB_DGND") (class "Default")
      (node (ref "C38") (pin "2") (pintype "passive"))
      (node (ref "C39") (pin "2") (pintype "passive"))
      (node (ref "C40") (pin "2") (pintype "passive"))
      (node (ref "C41") (pin "2") (pintype "passive"))
      (node (ref "C42") (pin "2") (pintype "passive"))
      (node (ref "C43") (pin "2") (pintype "passive"))
      (node (ref "C44") (pin "2") (pintype "passive"))
      (node (ref "C45") (pin "2") (pintype "passive"))
      (node (ref "C46") (pin "2") (pintype "passive"))
      (node (ref "C47") (pin "2") (pintype "passive"))
      (node (ref "C48") (pin "2") (pintype "passive"))
      (node (ref "C49") (pin "2") (pintype "passive"))
      (node (ref "C50") (pin "2") (pintype "passive"))
      (node (ref "C51") (pin "2") (pintype "passive"))
      (node (ref "C52") (pin "2") (pintype "passive"))
      (node (ref "C53") (pin "2") (pintype "passive"))
      (node (ref "C54") (pin "2") (pintype "passive"))
      (node (ref "C55") (pin "2") (pintype "passive"))
      (node (ref "C56") (pin "2") (pintype "passive"))
      (node (ref "C57") (pin "2") (pintype "passive"))
      (node (ref "C58") (pin "2") (pintype "passive"))
      (node (ref "C59") (pin "2") (pintype "passive"))
      (node (ref "C60") (pin "2") (pintype "passive"))
      (node (ref "C61") (pin "2") (pintype "passive"))
      (node (ref "C62") (pin "2") (pintype "passive"))
      (node (ref "C63") (pin "2") (pintype "passive"))
      (node (ref "J18") (pin "C01") (pinfunction "C01_C01") (pintype "passive"))
      (node (ref "J18") (pin "C04") (pinfunction "C04_C04") (pintype "passive"))
      (node (ref "J18") (pin "C05") (pinfunction "C05_C05") (pintype "passive"))
      (node (ref "J18") (pin "C08") (pinfunction "C08_C08") (pintype "passive"))
      (node (ref "J18") (pin "C09") (pinfunction "C09_C09") (pintype "passive"))
      (node (ref "J18") (pin "C12") (pinfunction "C12_C12") (pintype "passive"))
      (node (ref "J18") (pin "C13") (pinfunction "C13_C13") (pintype "passive"))
      (node (ref "J18") (pin "C16") (pinfunction "C16_C16") (pintype "passive"))
      (node (ref "J18") (pin "C17") (pinfunction "C17_C17") (pintype "passive"))
      (node (ref "J18") (pin "C20") (pinfunction "C20_C20") (pintype "passive"))
      (node (ref "J18") (pin "C21") (pinfunction "C21_C21") (pintype "passive"))
      (node (ref "J18") (pin "C24") (pinfunction "C24_C24") (pintype "passive"))
      (node (ref "J18") (pin "C25") (pinfunction "C25_C25") (pintype "passive"))
      (node (ref "J18") (pin "C28") (pinfunction "C28_C28") (pintype "passive"))
      (node (ref "J18") (pin "C29") (pinfunction "C29_C29") (pintype "passive"))
      (node (ref "J18") (pin "C32") (pinfunction "C32_C32") (pintype "passive"))
      (node (ref "J18") (pin "C33") (pinfunction "C33_C33") (pintype "passive"))
      (node (ref "J18") (pin "C36") (pinfunction "C36_C36") (pintype "passive"))
      (node (ref "J18") (pin "C38") (pinfunction "C38_C38") (pintype "passive"))
      (node (ref "J18") (pin "C40") (pinfunction "C40_C40") (pintype "passive"))
      (node (ref "J18") (pin "D02") (pinfunction "D02_D02") (pintype "passive"))
      (node (ref "J18") (pin "D03") (pinfunction "D03_D03") (pintype "passive"))
      (node (ref "J18") (pin "D06") (pinfunction "D06_D06") (pintype "passive"))
      (node (ref "J18") (pin "D07") (pinfunction "D07_D07") (pintype "passive"))
      (node (ref "J18") (pin "D10") (pinfunction "D10_D10") (pintype "passive"))
      (node (ref "J18") (pin "D13") (pinfunction "D13_D13") (pintype "passive"))
      (node (ref "J18") (pin "D16") (pinfunction "D16_D16") (pintype "passive"))
      (node (ref "J18") (pin "D19") (pinfunction "D19_D19") (pintype "passive"))
      (node (ref "J18") (pin "D22") (pinfunction "D22_D22") (pintype "passive"))
      (node (ref "J18") (pin "D25") (pinfunction "D25_D25") (pintype "passive"))
      (node (ref "J18") (pin "D28") (pinfunction "D28_D28") (pintype "passive"))
      (node (ref "J18") (pin "D37") (pinfunction "D37_D37") (pintype "passive"))
      (node (ref "J18") (pin "D39") (pinfunction "D39_D39") (pintype "passive"))
      (node (ref "J18") (pin "G01") (pinfunction "G01_G01") (pintype "passive"))
      (node (ref "J18") (pin "G04") (pinfunction "G04_G04") (pintype "passive"))
      (node (ref "J18") (pin "G05") (pinfunction "G05_G05") (pintype "passive"))
      (node (ref "J18") (pin "G08") (pinfunction "G08_G08") (pintype "passive"))
      (node (ref "J18") (pin "G11") (pinfunction "G11_G11") (pintype "passive"))
      (node (ref "J18") (pin "G14") (pinfunction "G14_G14") (pintype "passive"))
      (node (ref "J18") (pin "G17") (pinfunction "G17_G17") (pintype "passive"))
      (node (ref "J18") (pin "G20") (pinfunction "G20_G20") (pintype "passive"))
      (node (ref "J18") (pin "G23") (pinfunction "G23_G23") (pintype "passive"))
      (node (ref "J18") (pin "G26") (pinfunction "G26_G26") (pintype "passive"))
      (node (ref "J18") (pin "G29") (pinfunction "G29_G29") (pintype "passive"))
      (node (ref "J18") (pin "G32") (pinfunction "G32_G32") (pintype "passive"))
      (node (ref "J18") (pin "G35") (pinfunction "G35_G35") (pintype "passive"))
      (node (ref "J18") (pin "G38") (pinfunction "G38_G38") (pintype "passive"))
      (node (ref "J18") (pin "G40") (pinfunction "G40_G40") (pintype "passive"))
      (node (ref "J18") (pin "H03") (pinfunction "H03_H03") (pintype "passive"))
      (node (ref "J18") (pin "H06") (pinfunction "H06_H06") (pintype "passive"))
      (node (ref "J18") (pin "H09") (pinfunction "H09_H09") (pintype "passive"))
      (node (ref "J18") (pin "H12") (pinfunction "H12_H12") (pintype "passive"))
      (node (ref "J18") (pin "H15") (pinfunction "H15_H15") (pintype "passive"))
      (node (ref "J18") (pin "H18") (pinfunction "H18_H18") (pintype "passive"))
      (node (ref "J18") (pin "H21") (pinfunction "H21_H21") (pintype "passive"))
      (node (ref "J18") (pin "H24") (pinfunction "H24_H24") (pintype "passive"))
      (node (ref "J18") (pin "H27") (pinfunction "H27_H27") (pintype "passive"))
      (node (ref "J18") (pin "H30") (pinfunction "H30_H30") (pintype "passive"))
      (node (ref "J18") (pin "H33") (pinfunction "H33_H33") (pintype "passive"))
      (node (ref "J18") (pin "H36") (pinfunction "H36_H36") (pintype "passive"))
      (node (ref "J18") (pin "H39") (pinfunction "H39_H39") (pintype "passive"))
      (node (ref "J19") (pin "11") (pinfunction "11_11") (pintype "passive"))
      (node (ref "J19") (pin "12") (pinfunction "12_12") (pintype "passive"))
      (node (ref "J19") (pin "14") (pinfunction "14_14") (pintype "passive"))
      (node (ref "J19") (pin "15") (pinfunction "15_15") (pintype "passive"))
      (node (ref "J19") (pin "17") (pinfunction "17_17") (pintype "passive"))
      (node (ref "J19") (pin "18") (pinfunction "18_18") (pintype "passive"))
      (node (ref "J19") (pin "2") (pinfunction "2_2") (pintype "passive"))
      (node (ref "J19") (pin "20") (pinfunction "20_20") (pintype "passive"))
      (node (ref "J19") (pin "21") (pinfunction "21_21") (pintype "passive"))
      (node (ref "J19") (pin "23") (pinfunction "23_23") (pintype "passive"))
      (node (ref "J19") (pin "24") (pinfunction "24_24") (pintype "passive"))
      (node (ref "J19") (pin "26") (pinfunction "26_26") (pintype "passive"))
      (node (ref "J19") (pin "27") (pinfunction "27_27") (pintype "passive"))
      (node (ref "J19") (pin "29") (pinfunction "29_29") (pintype "passive"))
      (node (ref "J19") (pin "3") (pinfunction "3_3") (pintype "passive"))
      (node (ref "J19") (pin "30") (pinfunction "30_30") (pintype "passive"))
      (node (ref "J19") (pin "32") (pinfunction "32_32") (pintype "passive"))
      (node (ref "J19") (pin "33") (pinfunction "33_33") (pintype "passive"))
      (node (ref "J19") (pin "35") (pinfunction "35_35") (pintype "passive"))
      (node (ref "J19") (pin "36") (pinfunction "36_36") (pintype "passive"))
      (node (ref "J19") (pin "38") (pinfunction "38_38") (pintype "passive"))
      (node (ref "J19") (pin "39") (pinfunction "39_39") (pintype "passive"))
      (node (ref "J19") (pin "41") (pinfunction "41_41") (pintype "passive"))
      (node (ref "J19") (pin "42") (pinfunction "42_42") (pintype "passive"))
      (node (ref "J19") (pin "44") (pinfunction "44_44") (pintype "passive"))
      (node (ref "J19") (pin "45") (pinfunction "45_45") (pintype "passive"))
      (node (ref "J19") (pin "47") (pinfunction "47_47") (pintype "passive"))
      (node (ref "J19") (pin "48") (pinfunction "48_48") (pintype "passive"))
      (node (ref "J19") (pin "5") (pinfunction "5_5") (pintype "passive"))
      (node (ref "J19") (pin "50") (pinfunction "50_50") (pintype "passive"))
      (node (ref "J19") (pin "51") (pinfunction "51_51") (pintype "passive"))
      (node (ref "J19") (pin "53") (pinfunction "53_53") (pintype "passive"))
      (node (ref "J19") (pin "54") (pinfunction "54_54") (pintype "passive"))
      (node (ref "J19") (pin "56") (pinfunction "56_56") (pintype "passive"))
      (node (ref "J19") (pin "57") (pinfunction "57_57") (pintype "passive"))
      (node (ref "J19") (pin "59") (pinfunction "59_59") (pintype "passive"))
      (node (ref "J19") (pin "6") (pinfunction "6_6") (pintype "passive"))
      (node (ref "J19") (pin "60") (pinfunction "60_60") (pintype "passive"))
      (node (ref "J19") (pin "62") (pinfunction "62_62") (pintype "passive"))
      (node (ref "J19") (pin "63") (pinfunction "63_63") (pintype "passive"))
      (node (ref "J19") (pin "65") (pinfunction "65_65") (pintype "passive"))
      (node (ref "J19") (pin "66") (pinfunction "66_66") (pintype "passive"))
      (node (ref "J19") (pin "68") (pinfunction "68_68") (pintype "passive"))
      (node (ref "J19") (pin "69") (pinfunction "69_69") (pintype "passive"))
      (node (ref "J19") (pin "71") (pinfunction "71_71") (pintype "passive"))
      (node (ref "J19") (pin "72") (pinfunction "72_72") (pintype "passive"))
      (node (ref "J19") (pin "74") (pinfunction "74_74") (pintype "passive"))
      (node (ref "J19") (pin "75") (pinfunction "75_75") (pintype "passive"))
      (node (ref "J19") (pin "77") (pinfunction "77_77") (pintype "passive"))
      (node (ref "J19") (pin "78") (pinfunction "78_78") (pintype "passive"))
      (node (ref "J19") (pin "79") (pinfunction "79_79") (pintype "passive"))
      (node (ref "J19") (pin "8") (pinfunction "8_8") (pintype "passive"))
      (node (ref "J19") (pin "80") (pinfunction "80_80") (pintype "passive"))
      (node (ref "J19") (pin "81") (pinfunction "81_81") (pintype "passive"))
      (node (ref "J19") (pin "82") (pinfunction "82_82") (pintype "passive"))
      (node (ref "J19") (pin "83") (pinfunction "83_83") (pintype "passive"))
      (node (ref "J19") (pin "84") (pinfunction "84_84") (pintype "passive"))
      (node (ref "J19") (pin "85") (pinfunction "85_85") (pintype "passive"))
      (node (ref "J19") (pin "86") (pinfunction "86_86") (pintype "passive"))
      (node (ref "J19") (pin "87") (pinfunction "87_87") (pintype "passive"))
      (node (ref "J19") (pin "88") (pinfunction "88_88") (pintype "passive"))
      (node (ref "J19") (pin "89") (pinfunction "89_89") (pintype "passive"))
      (node (ref "J19") (pin "9") (pinfunction "9_9") (pintype "passive"))
      (node (ref "J19") (pin "90") (pinfunction "90_90") (pintype "passive"))
      (node (ref "J19") (pin "91") (pinfunction "91_91") (pintype "passive"))
      (node (ref "J19") (pin "92") (pinfunction "92_92") (pintype "passive"))
      (node (ref "J19") (pin "93") (pinfunction "93_93") (pintype "passive"))
      (node (ref "J19") (pin "94") (pinfunction "94_94") (pintype "passive"))
      (node (ref "J19") (pin "95") (pinfunction "95_95") (pintype "passive"))
      (node (ref "J19") (pin "96") (pinfunction "96_96") (pintype "passive"))
      (node (ref "P40") (pin "2") (pinfunction "2_2") (pintype "passive"))
      (node (ref "P41") (pin "2") (pinfunction "2_2") (pintype "passive"))
      (node (ref "P42") (pin "2") (pinfunction "2_2") (pintype "passive"))
      (node (ref "P43") (pin "2") (pinfunction "2_2") (pintype "passive"))
      (node (ref "U37") (pin "3") (pinfunction "GND_3") (pintype "power_in"))
      (node (ref "U38") (pin "3") (pinfunction "GND_3") (pintype "power_in"))
      (node (ref "U39") (pin "3") (pinfunction "GND_3") (pintype "power_in"))
      (node (ref "U40") (pin "3") (pinfunction "GND_3") (pintype "power_in"))
      (node (ref "U41") (pin "3") (pinfunction "GND_3") (pintype "power_in"))
      (node (ref "U42") (pin "3") (pinfunction "GND_3") (pintype "power_in"))
      (node (ref "U43") (pin "3") (pinfunction "GND_3") (pintype "power_in"))
      (node (ref "U44") (pin "3") (pinfunction "GND_3") (pintype "power_in"))
      (node (ref "U45") (pin "3") (pinfunction "GND_3") (pintype "power_in"))
      (node (ref "U46") (pin "3") (pinfunction "GND_3") (pintype "power_in"))
      (node (ref "U47") (pin "3") (pinfunction "GND_3") (pintype "power_in"))
      (node (ref "U48") (pin "3") (pinfunction "GND_3") (pintype "power_in"))
      (node (ref "U49") (pin "3") (pinfunction "GND_3") (pintype "power_in"))
      (node (ref "U50") (pin "GND1") (pinfunction "GND_GND1") (pintype "power_in"))
      (node (ref "U50") (pin "GND2") (pinfunction "GND_GND2") (pintype "power_in"))
      (node (ref "U50") (pin "GND3") (pinfunction "GND_GND3") (pintype "power_in"))
      (node (ref "U50") (pin "GND4") (pinfunction "GND_GND4") (pintype "power_in"))
      (node (ref "U50") (pin "GND5") (pinfunction "GND_GND5") (pintype "power_in"))
      (node (ref "U51") (pin "GND1") (pinfunction "GND_GND1") (pintype "power_in"))
      (node (ref "U51") (pin "GND2") (pinfunction "GND_GND2") (pintype "power_in"))
      (node (ref "U51") (pin "GND3") (pinfunction "GND_GND3") (pintype "power_in"))
      (node (ref "U51") (pin "GND4") (pinfunction "GND_GND4") (pintype "power_in"))
      (node (ref "U51") (pin "GND5") (pinfunction "GND_GND5") (pintype "power_in"))
    )
    (net (code "68") (name "VDD_3P3V_IN") (class "Default")
      (node (ref "C38") (pin "1") (pintype "passive"))
      (node (ref "C39") (pin "1") (pintype "passive"))
      (node (ref "C40") (pin "1") (pintype "passive"))
      (node (ref "C41") (pin "1") (pintype "passive"))
      (node (ref "C42") (pin "1") (pintype "passive"))
      (node (ref "C43") (pin "1") (pintype "passive"))
      (node (ref "C44") (pin "1") (pintype "passive"))
      (node (ref "C45") (pin "1") (pintype "passive"))
      (node (ref "C46") (pin "1") (pintype "passive"))
      (node (ref "C47") (pin "1") (pintype "passive"))
      (node (ref "C48") (pin "1") (pintype "passive"))
      (node (ref "C49") (pin "1") (pintype "passive"))
      (node (ref "C50") (pin "1") (pintype "passive"))
      (node (ref "C51") (pin "1") (pintype "passive"))
      (node (ref "C52") (pin "1") (pintype "passive"))
      (node (ref "C53") (pin "1") (pintype "passive"))
      (node (ref "C54") (pin "1") (pintype "passive"))
      (node (ref "C55") (pin "1") (pintype "passive"))
      (node (ref "C56") (pin "1") (pintype "passive"))
      (node (ref "C57") (pin "1") (pintype "passive"))
      (node (ref "C58") (pin "1") (pintype "passive"))
      (node (ref "C59") (pin "1") (pintype "passive"))
      (node (ref "C60") (pin "1") (pintype "passive"))
      (node (ref "C61") (pin "1") (pintype "passive"))
      (node (ref "C62") (pin "1") (pintype "passive"))
      (node (ref "C63") (pin "1") (pintype "passive"))
      (node (ref "U37") (pin "5") (pinfunction "VCC_5") (pintype "power_in"))
      (node (ref "U38") (pin "5") (pinfunction "VCC_5") (pintype "power_in"))
      (node (ref "U39") (pin "5") (pinfunction "VCC_5") (pintype "power_in"))
      (node (ref "U40") (pin "5") (pinfunction "VCC_5") (pintype "power_in"))
      (node (ref "U41") (pin "5") (pinfunction "VCC_5") (pintype "power_in"))
      (node (ref "U42") (pin "5") (pinfunction "VCC_5") (pintype "power_in"))
      (node (ref "U43") (pin "5") (pinfunction "VCC_5") (pintype "power_in"))
      (node (ref "U44") (pin "5") (pinfunction "VCC_5") (pintype "power_in"))
      (node (ref "U45") (pin "5") (pinfunction "VCC_5") (pintype "power_in"))
      (node (ref "U46") (pin "5") (pinfunction "VCC_5") (pintype "power_in"))
      (node (ref "U47") (pin "5") (pinfunction "VCC_5") (pintype "power_in"))
      (node (ref "U48") (pin "5") (pinfunction "VCC_5") (pintype "power_in"))
      (node (ref "U49") (pin "5") (pinfunction "VCC_5") (pintype "power_in"))
    )
    (net (code "69") (name "unconnected-(J18-PadC02)") (class "Default")
      (node (ref "J18") (pin "C02") (pinfunction "C02_C02") (pintype "passive"))
    )
    (net (code "70") (name "unconnected-(J18-PadC03)") (class "Default")
      (node (ref "J18") (pin "C03") (pinfunction "C03_C03") (pintype "passive"))
    )
    (net (code "71") (name "unconnected-(J18-PadC06)") (class "Default")
      (node (ref "J18") (pin "C06") (pinfunction "C06_C06") (pintype "passive"))
    )
    (net (code "72") (name "unconnected-(J18-PadC07)") (class "Default")
      (node (ref "J18") (pin "C07") (pinfunction "C07_C07") (pintype "passive"))
    )
    (net (code "73") (name "unconnected-(J18-PadC31)") (class "Default")
      (node (ref "J18") (pin "C31") (pinfunction "C31_C31") (pintype "passive"))
    )
    (net (code "74") (name "unconnected-(J18-PadC34)") (class "Default")
      (node (ref "J18") (pin "C34") (pinfunction "C34_C34") (pintype "passive"))
    )
    (net (code "75") (name "unconnected-(J18-PadC37)") (class "Default")
      (node (ref "J18") (pin "C37") (pinfunction "C37_C37") (pintype "passive"))
    )
    (net (code "76") (name "unconnected-(J18-PadD01)") (class "Default")
      (node (ref "J18") (pin "D01") (pinfunction "D01_D01") (pintype "passive"))
    )
    (net (code "77") (name "unconnected-(J18-PadD04)") (class "Default")
      (node (ref "J18") (pin "D04") (pinfunction "D04_D04") (pintype "passive"))
    )
    (net (code "78") (name "unconnected-(J18-PadD05)") (class "Default")
      (node (ref "J18") (pin "D05") (pinfunction "D05_D05") (pintype "passive"))
    )
    (net (code "79") (name "unconnected-(J18-PadD08)") (class "Default")
      (node (ref "J18") (pin "D08") (pinfunction "D08_D08") (pintype "passive"))
    )
    (net (code "80") (name "unconnected-(J18-PadD29)") (class "Default")
      (node (ref "J18") (pin "D29") (pinfunction "D29_D29") (pintype "passive"))
    )
    (net (code "81") (name "unconnected-(J18-PadD30)") (class "Default")
      (node (ref "J18") (pin "D30") (pinfunction "D30_D30") (pintype "passive"))
    )
    (net (code "82") (name "unconnected-(J18-PadD31)") (class "Default")
      (node (ref "J18") (pin "D31") (pinfunction "D31_D31") (pintype "passive"))
    )
    (net (code "83") (name "unconnected-(J18-PadD32)") (class "Default")
      (node (ref "J18") (pin "D32") (pinfunction "D32_D32") (pintype "passive"))
    )
    (net (code "84") (name "unconnected-(J18-PadD33)") (class "Default")
      (node (ref "J18") (pin "D33") (pinfunction "D33_D33") (pintype "passive"))
    )
    (net (code "85") (name "unconnected-(J18-PadD34)") (class "Default")
      (node (ref "J18") (pin "D34") (pinfunction "D34_D34") (pintype "passive"))
    )
    (net (code "86") (name "unconnected-(J18-PadD35)") (class "Default")
      (node (ref "J18") (pin "D35") (pinfunction "D35_D35") (pintype "passive"))
    )
    (net (code "87") (name "unconnected-(J18-PadD36)") (class "Default")
      (node (ref "J18") (pin "D36") (pinfunction "D36_D36") (pintype "passive"))
    )
    (net (code "88") (name "unconnected-(J18-PadD38)") (class "Default")
      (node (ref "J18") (pin "D38") (pinfunction "D38_D38") (pintype "passive"))
    )
    (net (code "89") (name "unconnected-(J18-PadD40)") (class "Default")
      (node (ref "J18") (pin "D40") (pinfunction "D40_D40") (pintype "passive"))
    )
    (net (code "90") (name "unconnected-(J18-PadG02)") (class "Default")
      (node (ref "J18") (pin "G02") (pinfunction "G02_G02") (pintype "passive"))
    )
    (net (code "91") (name "unconnected-(J18-PadG03)") (class "Default")
      (node (ref "J18") (pin "G03") (pinfunction "G03_G03") (pintype "passive"))
    )
    (net (code "92") (name "unconnected-(J18-PadG37)") (class "Default")
      (node (ref "J18") (pin "G37") (pinfunction "G37_G37") (pintype "passive"))
    )
    (net (code "93") (name "unconnected-(J18-PadH01)") (class "Default")
      (node (ref "J18") (pin "H01") (pinfunction "H01_H01") (pintype "passive"))
    )
    (net (code "94") (name "unconnected-(J18-PadH02)") (class "Default")
      (node (ref "J18") (pin "H02") (pinfunction "H02_H02") (pintype "passive"))
    )
    (net (code "95") (name "unconnected-(J18-PadH08)") (class "Default")
      (node (ref "J18") (pin "H08") (pinfunction "H08_H08") (pintype "passive"))
    )
    (net (code "96") (name "unconnected-(J18-PadH10)") (class "Default")
      (node (ref "J18") (pin "H10") (pinfunction "H10_H10") (pintype "passive"))
    )
    (net (code "97") (name "unconnected-(J18-PadH11)") (class "Default")
      (node (ref "J18") (pin "H11") (pinfunction "H11_H11") (pintype "passive"))
    )
    (net (code "98") (name "unconnected-(J18-PadH13)") (class "Default")
      (node (ref "J18") (pin "H13") (pinfunction "H13_H13") (pintype "passive"))
    )
    (net (code "99") (name "unconnected-(J18-PadH14)") (class "Default")
      (node (ref "J18") (pin "H14") (pinfunction "H14_H14") (pintype "passive"))
    )
    (net (code "100") (name "unconnected-(J18-PadH16)") (class "Default")
      (node (ref "J18") (pin "H16") (pinfunction "H16_H16") (pintype "passive"))
    )
    (net (code "101") (name "unconnected-(J18-PadH17)") (class "Default")
      (node (ref "J18") (pin "H17") (pinfunction "H17_H17") (pintype "passive"))
    )
    (net (code "102") (name "unconnected-(J18-PadH19)") (class "Default")
      (node (ref "J18") (pin "H19") (pinfunction "H19_H19") (pintype "passive"))
    )
    (net (code "103") (name "unconnected-(J18-PadH20)") (class "Default")
      (node (ref "J18") (pin "H20") (pinfunction "H20_H20") (pintype "passive"))
    )
    (net (code "104") (name "unconnected-(J18-PadH22)") (class "Default")
      (node (ref "J18") (pin "H22") (pinfunction "H22_H22") (pintype "passive"))
    )
    (net (code "105") (name "unconnected-(J18-PadH23)") (class "Default")
      (node (ref "J18") (pin "H23") (pinfunction "H23_H23") (pintype "passive"))
    )
    (net (code "106") (name "unconnected-(J18-PadH25)") (class "Default")
      (node (ref "J18") (pin "H25") (pinfunction "H25_H25") (pintype "passive"))
    )
    (net (code "107") (name "unconnected-(J18-PadH26)") (class "Default")
      (node (ref "J18") (pin "H26") (pinfunction "H26_H26") (pintype "passive"))
    )
    (net (code "108") (name "unconnected-(J18-PadH28)") (class "Default")
      (node (ref "J18") (pin "H28") (pinfunction "H28_H28") (pintype "passive"))
    )
    (net (code "109") (name "unconnected-(J18-PadH29)") (class "Default")
      (node (ref "J18") (pin "H29") (pinfunction "H29_H29") (pintype "passive"))
    )
    (net (code "110") (name "unconnected-(J18-PadH31)") (class "Default")
      (node (ref "J18") (pin "H31") (pinfunction "H31_H31") (pintype "passive"))
    )
    (net (code "111") (name "unconnected-(J18-PadH32)") (class "Default")
      (node (ref "J18") (pin "H32") (pinfunction "H32_H32") (pintype "passive"))
    )
    (net (code "112") (name "unconnected-(J18-PadH34)") (class "Default")
      (node (ref "J18") (pin "H34") (pinfunction "H34_H34") (pintype "passive"))
    )
    (net (code "113") (name "unconnected-(J18-PadH35)") (class "Default")
      (node (ref "J18") (pin "H35") (pinfunction "H35_H35") (pintype "passive"))
    )
    (net (code "114") (name "unconnected-(J18-PadH37)") (class "Default")
      (node (ref "J18") (pin "H37") (pinfunction "H37_H37") (pintype "passive"))
    )
    (net (code "115") (name "unconnected-(J18-PadH38)") (class "Default")
      (node (ref "J18") (pin "H38") (pinfunction "H38_H38") (pintype "passive"))
    )
    (net (code "116") (name "unconnected-(J18-PadH40)") (class "Default")
      (node (ref "J18") (pin "H40") (pinfunction "H40_H40") (pintype "passive"))
    )
    (net (code "117") (name "unconnected-(U37-NC-Pad1)") (class "Default")
      (node (ref "U37") (pin "1") (pinfunction "NC_1") (pintype "passive"))
    )
    (net (code "118") (name "unconnected-(U38-NC-Pad1)") (class "Default")
      (node (ref "U38") (pin "1") (pinfunction "NC_1") (pintype "passive"))
    )
    (net (code "119") (name "unconnected-(U39-NC-Pad1)") (class "Default")
      (node (ref "U39") (pin "1") (pinfunction "NC_1") (pintype "passive"))
    )
    (net (code "120") (name "unconnected-(U40-NC-Pad1)") (class "Default")
      (node (ref "U40") (pin "1") (pinfunction "NC_1") (pintype "passive"))
    )
    (net (code "121") (name "unconnected-(U41-NC-Pad1)") (class "Default")
      (node (ref "U41") (pin "1") (pinfunction "NC_1") (pintype "passive"))
    )
    (net (code "122") (name "unconnected-(U42-NC-Pad1)") (class "Default")
      (node (ref "U42") (pin "1") (pinfunction "NC_1") (pintype "passive"))
    )
    (net (code "123") (name "unconnected-(U43-NC-Pad1)") (class "Default")
      (node (ref "U43") (pin "1") (pinfunction "NC_1") (pintype "passive"))
    )
    (net (code "124") (name "unconnected-(U44-NC-Pad1)") (class "Default")
      (node (ref "U44") (pin "1") (pinfunction "NC_1") (pintype "passive"))
    )
    (net (code "125") (name "unconnected-(U45-NC-Pad1)") (class "Default")
      (node (ref "U45") (pin "1") (pinfunction "NC_1") (pintype "passive"))
    )
    (net (code "126") (name "unconnected-(U46-NC-Pad1)") (class "Default")
      (node (ref "U46") (pin "1") (pinfunction "NC_1") (pintype "passive"))
    )
    (net (code "127") (name "unconnected-(U47-NC-Pad1)") (class "Default")
      (node (ref "U47") (pin "1") (pinfunction "NC_1") (pintype "passive"))
    )
    (net (code "128") (name "unconnected-(U48-NC-Pad1)") (class "Default")
      (node (ref "U48") (pin "1") (pinfunction "NC_1") (pintype "passive"))
    )
    (net (code "129") (name "unconnected-(U49-NC-Pad1)") (class "Default")
      (node (ref "U49") (pin "1") (pinfunction "NC_1") (pintype "passive"))
    )
    (net (code "130") (name "unconnected-(U50-3.3V-Pad3.3V_1)") (class "Default")
      (node (ref "U50") (pin "3.3V_1") (pinfunction "3.3V_3.3V_1") (pintype "power_in"))
    )
    (net (code "131") (name "unconnected-(U50-3.3V-Pad3.3V_2)") (class "Default")
      (node (ref "U50") (pin "3.3V_2") (pinfunction "3.3V_3.3V_2") (pintype "power_in"))
    )
    (net (code "132") (name "unconnected-(U50-3.3V-Pad3.3V_3)") (class "Default")
      (node (ref "U50") (pin "3.3V_3") (pinfunction "3.3V_3.3V_3") (pintype "power_in"))
    )
    (net (code "133") (name "unconnected-(U50-CTX3-Pad31)") (class "Default")
      (node (ref "U50") (pin "31") (pinfunction "CTX3_31") (pintype "bidirectional"))
    )
    (net (code "134") (name "unconnected-(U50-OUT1B-Pad32)") (class "Default")
      (node (ref "U50") (pin "32") (pinfunction "OUT1B_32") (pintype "output"))
    )
    (net (code "135") (name "unconnected-(U50-Pad5V)") (class "Default")
      (node (ref "U50") (pin "5V") (pinfunction "5V_5V") (pintype "power_in"))
    )
    (net (code "136") (name "unconnected-(U50-PadD+)") (class "Default")
      (node (ref "U50") (pin "D+") (pinfunction "D+_D+") (pintype "bidirectional"))
    )
    (net (code "137") (name "unconnected-(U50-PadD-)") (class "Default")
      (node (ref "U50") (pin "D-") (pinfunction "D-_D-") (pintype "bidirectional"))
    )
    (net (code "138") (name "unconnected-(U50-PadLED)") (class "Default")
      (node (ref "U50") (pin "LED") (pinfunction "LED_LED") (pintype "bidirectional"))
    )
    (net (code "139") (name "unconnected-(U50-PadON{slash}OFF)") (class "Default")
      (node (ref "U50") (pin "ON/OFF") (pinfunction "ON/OFF_ON/OFF") (pintype "bidirectional"))
    )
    (net (code "140") (name "unconnected-(U50-PadPROGRAM)") (class "Default")
      (node (ref "U50") (pin "PROGRAM") (pinfunction "PROGRAM_PROGRAM") (pintype "bidirectional"))
    )
    (net (code "141") (name "unconnected-(U50-PadR+)") (class "Default")
      (node (ref "U50") (pin "R+") (pinfunction "R+_R+") (pintype "bidirectional"))
    )
    (net (code "142") (name "unconnected-(U50-PadR-)") (class "Default")
      (node (ref "U50") (pin "R-") (pinfunction "R-_R-") (pintype "bidirectional"))
    )
    (net (code "143") (name "unconnected-(U50-PadT+)") (class "Default")
      (node (ref "U50") (pin "T+") (pinfunction "T+_T+") (pintype "bidirectional"))
    )
    (net (code "144") (name "unconnected-(U50-PadT-)") (class "Default")
      (node (ref "U50") (pin "T-") (pinfunction "T-_T-") (pintype "bidirectional"))
    )
    (net (code "145") (name "unconnected-(U50-PadVBAT)") (class "Default")
      (node (ref "U50") (pin "VBAT") (pinfunction "VBAT_VBAT") (pintype "passive"))
    )
    (net (code "146") (name "unconnected-(U50-PadVIN)") (class "Default")
      (node (ref "U50") (pin "VIN") (pinfunction "VIN_VIN") (pintype "input"))
    )
    (net (code "147") (name "unconnected-(U50-PadVUSB)") (class "Default")
      (node (ref "U50") (pin "VUSB") (pinfunction "VUSB_VUSB") (pintype "passive"))
    )
    (net (code "148") (name "unconnected-(U50-USB_GND-PadUSB_GND1)") (class "Default")
      (node (ref "U50") (pin "USB_GND1") (pinfunction "USB_GND_USB_GND1") (pintype "power_in"))
    )
    (net (code "149") (name "unconnected-(U50-USB_GND-PadUSB_GND2)") (class "Default")
      (node (ref "U50") (pin "USB_GND2") (pinfunction "USB_GND_USB_GND2") (pintype "power_in"))
    )
    (net (code "150") (name "unconnected-(U51-3.3V-Pad3.3V_1)") (class "Default")
      (node (ref "U51") (pin "3.3V_1") (pinfunction "3.3V_3.3V_1") (pintype "power_in"))
    )
    (net (code "151") (name "unconnected-(U51-3.3V-Pad3.3V_2)") (class "Default")
      (node (ref "U51") (pin "3.3V_2") (pinfunction "3.3V_3.3V_2") (pintype "power_in"))
    )
    (net (code "152") (name "unconnected-(U51-3.3V-Pad3.3V_3)") (class "Default")
      (node (ref "U51") (pin "3.3V_3") (pinfunction "3.3V_3.3V_3") (pintype "power_in"))
    )
    (net (code "153") (name "unconnected-(U51-A0-Pad14)") (class "Default")
      (node (ref "U51") (pin "14") (pinfunction "A0_14") (pintype "bidirectional"))
    )
    (net (code "154") (name "unconnected-(U51-A1-Pad15)") (class "Default")
      (node (ref "U51") (pin "15") (pinfunction "A1_15") (pintype "bidirectional"))
    )
    (net (code "155") (name "unconnected-(U51-A2-Pad16)") (class "Default")
      (node (ref "U51") (pin "16") (pinfunction "A2_16") (pintype "bidirectional"))
    )
    (net (code "156") (name "unconnected-(U51-A3-Pad17)") (class "Default")
      (node (ref "U51") (pin "17") (pinfunction "A3_17") (pintype "bidirectional"))
    )
    (net (code "157") (name "unconnected-(U51-A4-Pad18)") (class "Default")
      (node (ref "U51") (pin "18") (pinfunction "A4_18") (pintype "bidirectional"))
    )
    (net (code "158") (name "unconnected-(U51-A5-Pad19)") (class "Default")
      (node (ref "U51") (pin "19") (pinfunction "A5_19") (pintype "bidirectional"))
    )
    (net (code "159") (name "unconnected-(U51-A6-Pad20)") (class "Default")
      (node (ref "U51") (pin "20") (pinfunction "A6_20") (pintype "bidirectional"))
    )
    (net (code "160") (name "unconnected-(U51-A7-Pad21)") (class "Default")
      (node (ref "U51") (pin "21") (pinfunction "A7_21") (pintype "bidirectional"))
    )
    (net (code "161") (name "unconnected-(U51-A8-Pad22)") (class "Default")
      (node (ref "U51") (pin "22") (pinfunction "A8_22") (pintype "bidirectional"))
    )
    (net (code "162") (name "unconnected-(U51-A9-Pad23)") (class "Default")
      (node (ref "U51") (pin "23") (pinfunction "A9_23") (pintype "bidirectional"))
    )
    (net (code "163") (name "unconnected-(U51-A10-Pad24)") (class "Default")
      (node (ref "U51") (pin "24") (pinfunction "A10_24") (pintype "bidirectional"))
    )
    (net (code "164") (name "unconnected-(U51-A11-Pad25)") (class "Default")
      (node (ref "U51") (pin "25") (pinfunction "A11_25") (pintype "bidirectional"))
    )
    (net (code "165") (name "unconnected-(U51-A12-Pad26)") (class "Default")
      (node (ref "U51") (pin "26") (pinfunction "A12_26") (pintype "bidirectional"))
    )
    (net (code "166") (name "unconnected-(U51-A13-Pad27)") (class "Default")
      (node (ref "U51") (pin "27") (pinfunction "A13_27") (pintype "bidirectional"))
    )
    (net (code "167") (name "unconnected-(U51-A14-Pad38)") (class "Default")
      (node (ref "U51") (pin "38") (pinfunction "A14_38") (pintype "bidirectional"))
    )
    (net (code "168") (name "unconnected-(U51-A15-Pad39)") (class "Default")
      (node (ref "U51") (pin "39") (pinfunction "A15_39") (pintype "bidirectional"))
    )
    (net (code "169") (name "unconnected-(U51-A16-Pad40)") (class "Default")
      (node (ref "U51") (pin "40") (pinfunction "A16_40") (pintype "bidirectional"))
    )
    (net (code "170") (name "unconnected-(U51-A17-Pad41)") (class "Default")
      (node (ref "U51") (pin "41") (pinfunction "A17_41") (pintype "bidirectional"))
    )
    (net (code "171") (name "unconnected-(U51-CRX3-Pad30)") (class "Default")
      (node (ref "U51") (pin "30") (pinfunction "CRX3_30") (pintype "bidirectional"))
    )
    (net (code "172") (name "unconnected-(U51-CS1-Pad10)") (class "Default")
      (node (ref "U51") (pin "10") (pinfunction "CS1_10") (pintype "bidirectional"))
    )
    (net (code "173") (name "unconnected-(U51-CS2-Pad36)") (class "Default")
      (node (ref "U51") (pin "36") (pinfunction "CS2_36") (pintype "bidirectional"))
    )
    (net (code "174") (name "unconnected-(U51-CS3-Pad37)") (class "Default")
      (node (ref "U51") (pin "37") (pinfunction "CS3_37") (pintype "bidirectional"))
    )
    (net (code "175") (name "unconnected-(U51-CTX3-Pad31)") (class "Default")
      (node (ref "U51") (pin "31") (pinfunction "CTX3_31") (pintype "bidirectional"))
    )
    (net (code "176") (name "unconnected-(U51-MCLK2-Pad33)") (class "Default")
      (node (ref "U51") (pin "33") (pinfunction "MCLK2_33") (pintype "bidirectional"))
    )
    (net (code "177") (name "unconnected-(U51-MISO-Pad12)") (class "Default")
      (node (ref "U51") (pin "12") (pinfunction "MISO_12") (pintype "bidirectional"))
    )
    (net (code "178") (name "unconnected-(U51-MOSI-Pad11)") (class "Default")
      (node (ref "U51") (pin "11") (pinfunction "MOSI_11") (pintype "bidirectional"))
    )
    (net (code "179") (name "unconnected-(U51-OUT1B-Pad32)") (class "Default")
      (node (ref "U51") (pin "32") (pinfunction "OUT1B_32") (pintype "output"))
    )
    (net (code "180") (name "unconnected-(U51-OUT1C-Pad9)") (class "Default")
      (node (ref "U51") (pin "9") (pinfunction "OUT1C_9") (pintype "output"))
    )
    (net (code "181") (name "unconnected-(U51-Pad5V)") (class "Default")
      (node (ref "U51") (pin "5V") (pinfunction "5V_5V") (pintype "power_in"))
    )
    (net (code "182") (name "unconnected-(U51-PadD+)") (class "Default")
      (node (ref "U51") (pin "D+") (pinfunction "D+_D+") (pintype "bidirectional"))
    )
    (net (code "183") (name "unconnected-(U51-PadD-)") (class "Default")
      (node (ref "U51") (pin "D-") (pinfunction "D-_D-") (pintype "bidirectional"))
    )
    (net (code "184") (name "unconnected-(U51-PadLED)") (class "Default")
      (node (ref "U51") (pin "LED") (pinfunction "LED_LED") (pintype "bidirectional"))
    )
    (net (code "185") (name "unconnected-(U51-PadON{slash}OFF)") (class "Default")
      (node (ref "U51") (pin "ON/OFF") (pinfunction "ON/OFF_ON/OFF") (pintype "bidirectional"))
    )
    (net (code "186") (name "unconnected-(U51-PadPROGRAM)") (class "Default")
      (node (ref "U51") (pin "PROGRAM") (pinfunction "PROGRAM_PROGRAM") (pintype "bidirectional"))
    )
    (net (code "187") (name "unconnected-(U51-PadR+)") (class "Default")
      (node (ref "U51") (pin "R+") (pinfunction "R+_R+") (pintype "bidirectional"))
    )
    (net (code "188") (name "unconnected-(U51-PadR-)") (class "Default")
      (node (ref "U51") (pin "R-") (pinfunction "R-_R-") (pintype "bidirectional"))
    )
    (net (code "189") (name "unconnected-(U51-PadT+)") (class "Default")
      (node (ref "U51") (pin "T+") (pinfunction "T+_T+") (pintype "bidirectional"))
    )
    (net (code "190") (name "unconnected-(U51-PadT-)") (class "Default")
      (node (ref "U51") (pin "T-") (pinfunction "T-_T-") (pintype "bidirectional"))
    )
    (net (code "191") (name "unconnected-(U51-PadVBAT)") (class "Default")
      (node (ref "U51") (pin "VBAT") (pinfunction "VBAT_VBAT") (pintype "passive"))
    )
    (net (code "192") (name "unconnected-(U51-PadVIN)") (class "Default")
      (node (ref "U51") (pin "VIN") (pinfunction "VIN_VIN") (pintype "input"))
    )
    (net (code "193") (name "unconnected-(U51-PadVUSB)") (class "Default")
      (node (ref "U51") (pin "VUSB") (pinfunction "VUSB_VUSB") (pintype "passive"))
    )
    (net (code "194") (name "unconnected-(U51-RX7-Pad28)") (class "Default")
      (node (ref "U51") (pin "28") (pinfunction "RX7_28") (pintype "bidirectional"))
    )
    (net (code "195") (name "unconnected-(U51-RX8-Pad34)") (class "Default")
      (node (ref "U51") (pin "34") (pinfunction "RX8_34") (pintype "bidirectional"))
    )
    (net (code "196") (name "unconnected-(U51-SCK-Pad13)") (class "Default")
      (node (ref "U51") (pin "13") (pinfunction "SCK_13") (pintype "bidirectional"))
    )
    (net (code "197") (name "unconnected-(U51-TX2-Pad8)") (class "Default")
      (node (ref "U51") (pin "8") (pinfunction "TX2_8") (pintype "bidirectional"))
    )
    (net (code "198") (name "unconnected-(U51-TX7-Pad29)") (class "Default")
      (node (ref "U51") (pin "29") (pinfunction "TX7_29") (pintype "bidirectional"))
    )
    (net (code "199") (name "unconnected-(U51-TX8-Pad35)") (class "Default")
      (node (ref "U51") (pin "35") (pinfunction "TX8_35") (pintype "bidirectional"))
    )
    (net (code "200") (name "unconnected-(U51-USB_GND-PadUSB_GND1)") (class "Default")
      (node (ref "U51") (pin "USB_GND1") (pinfunction "USB_GND_USB_GND1") (pintype "power_in"))
    )
    (net (code "201") (name "unconnected-(U51-USB_GND-PadUSB_GND2)") (class "Default")
      (node (ref "U51") (pin "USB_GND2") (pinfunction "USB_GND_USB_GND2") (pintype "power_in"))
    )
  )
)
